# 202405272.net
KiCad netlist of a schematic drawn in EAGLE
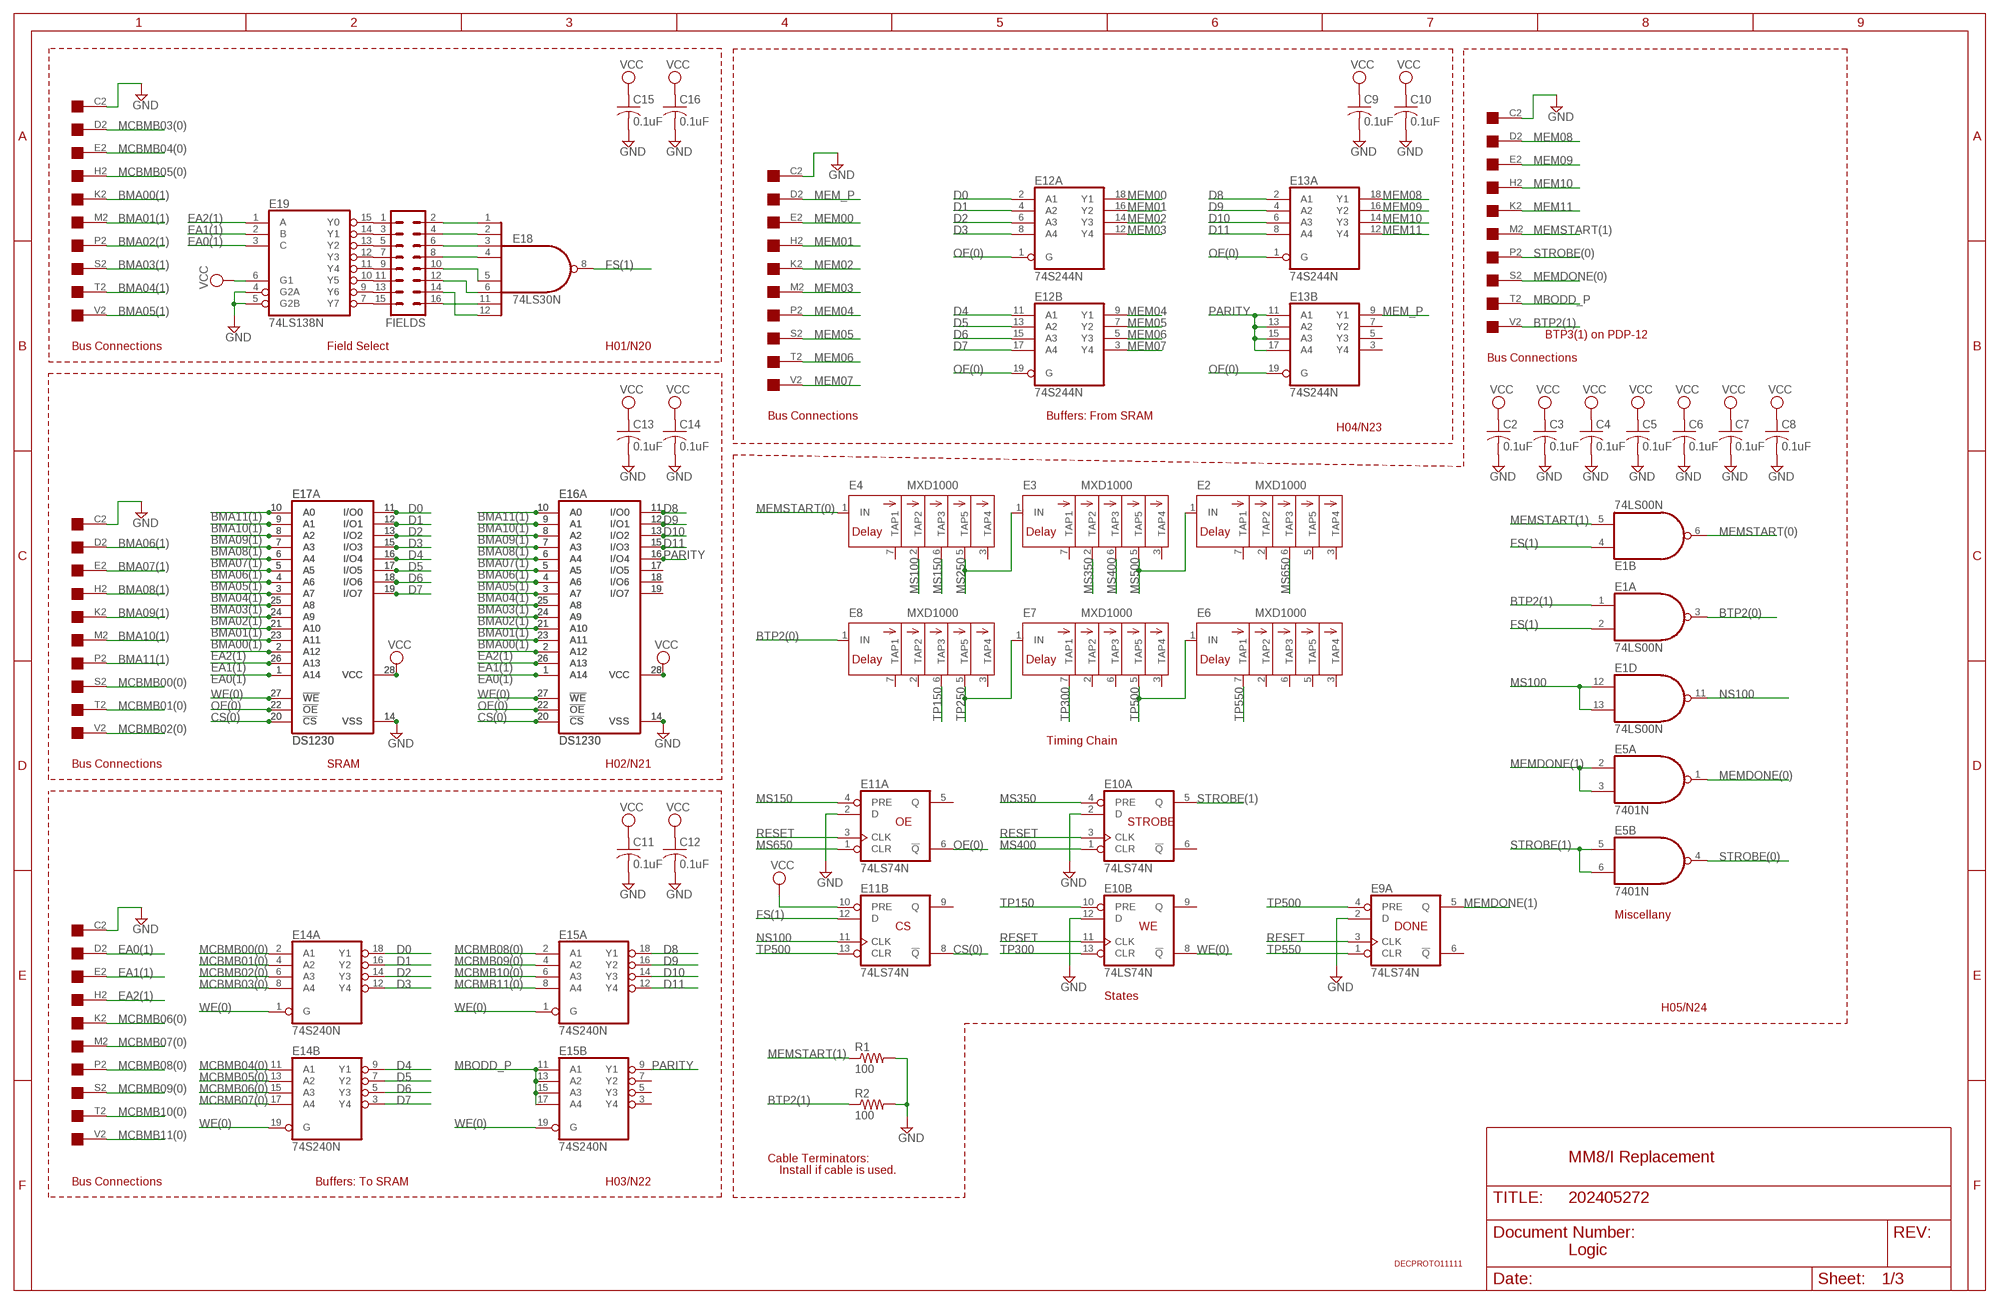
[diagram p0: schematic, sheet 1]
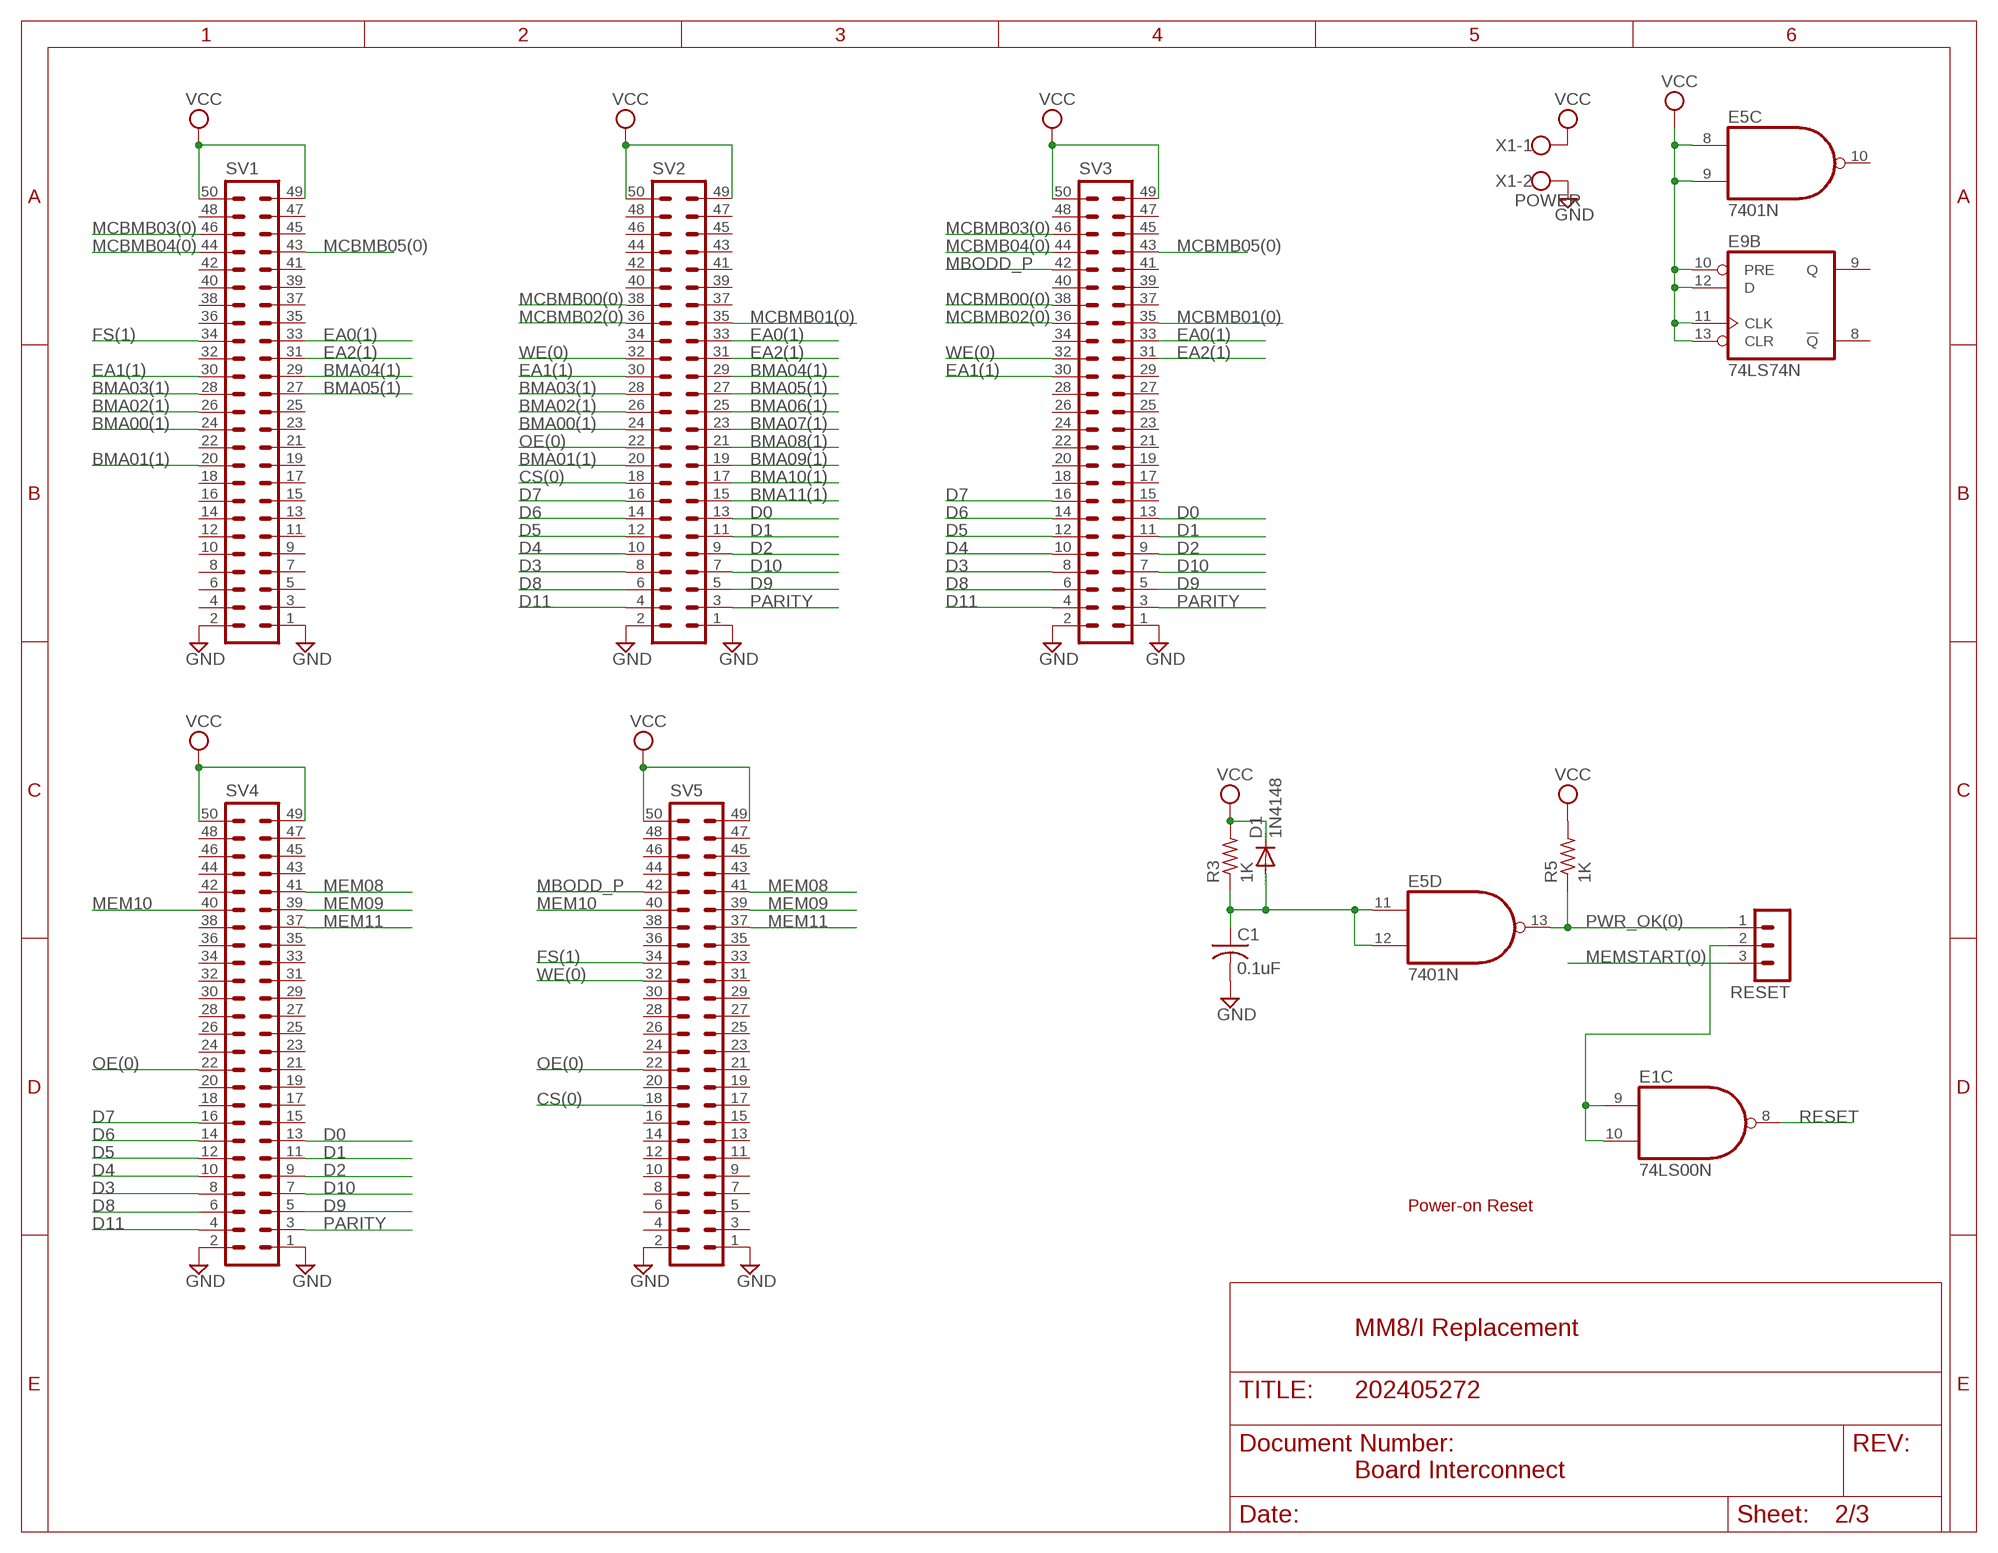
[diagram p1: schematic, sheet 2]
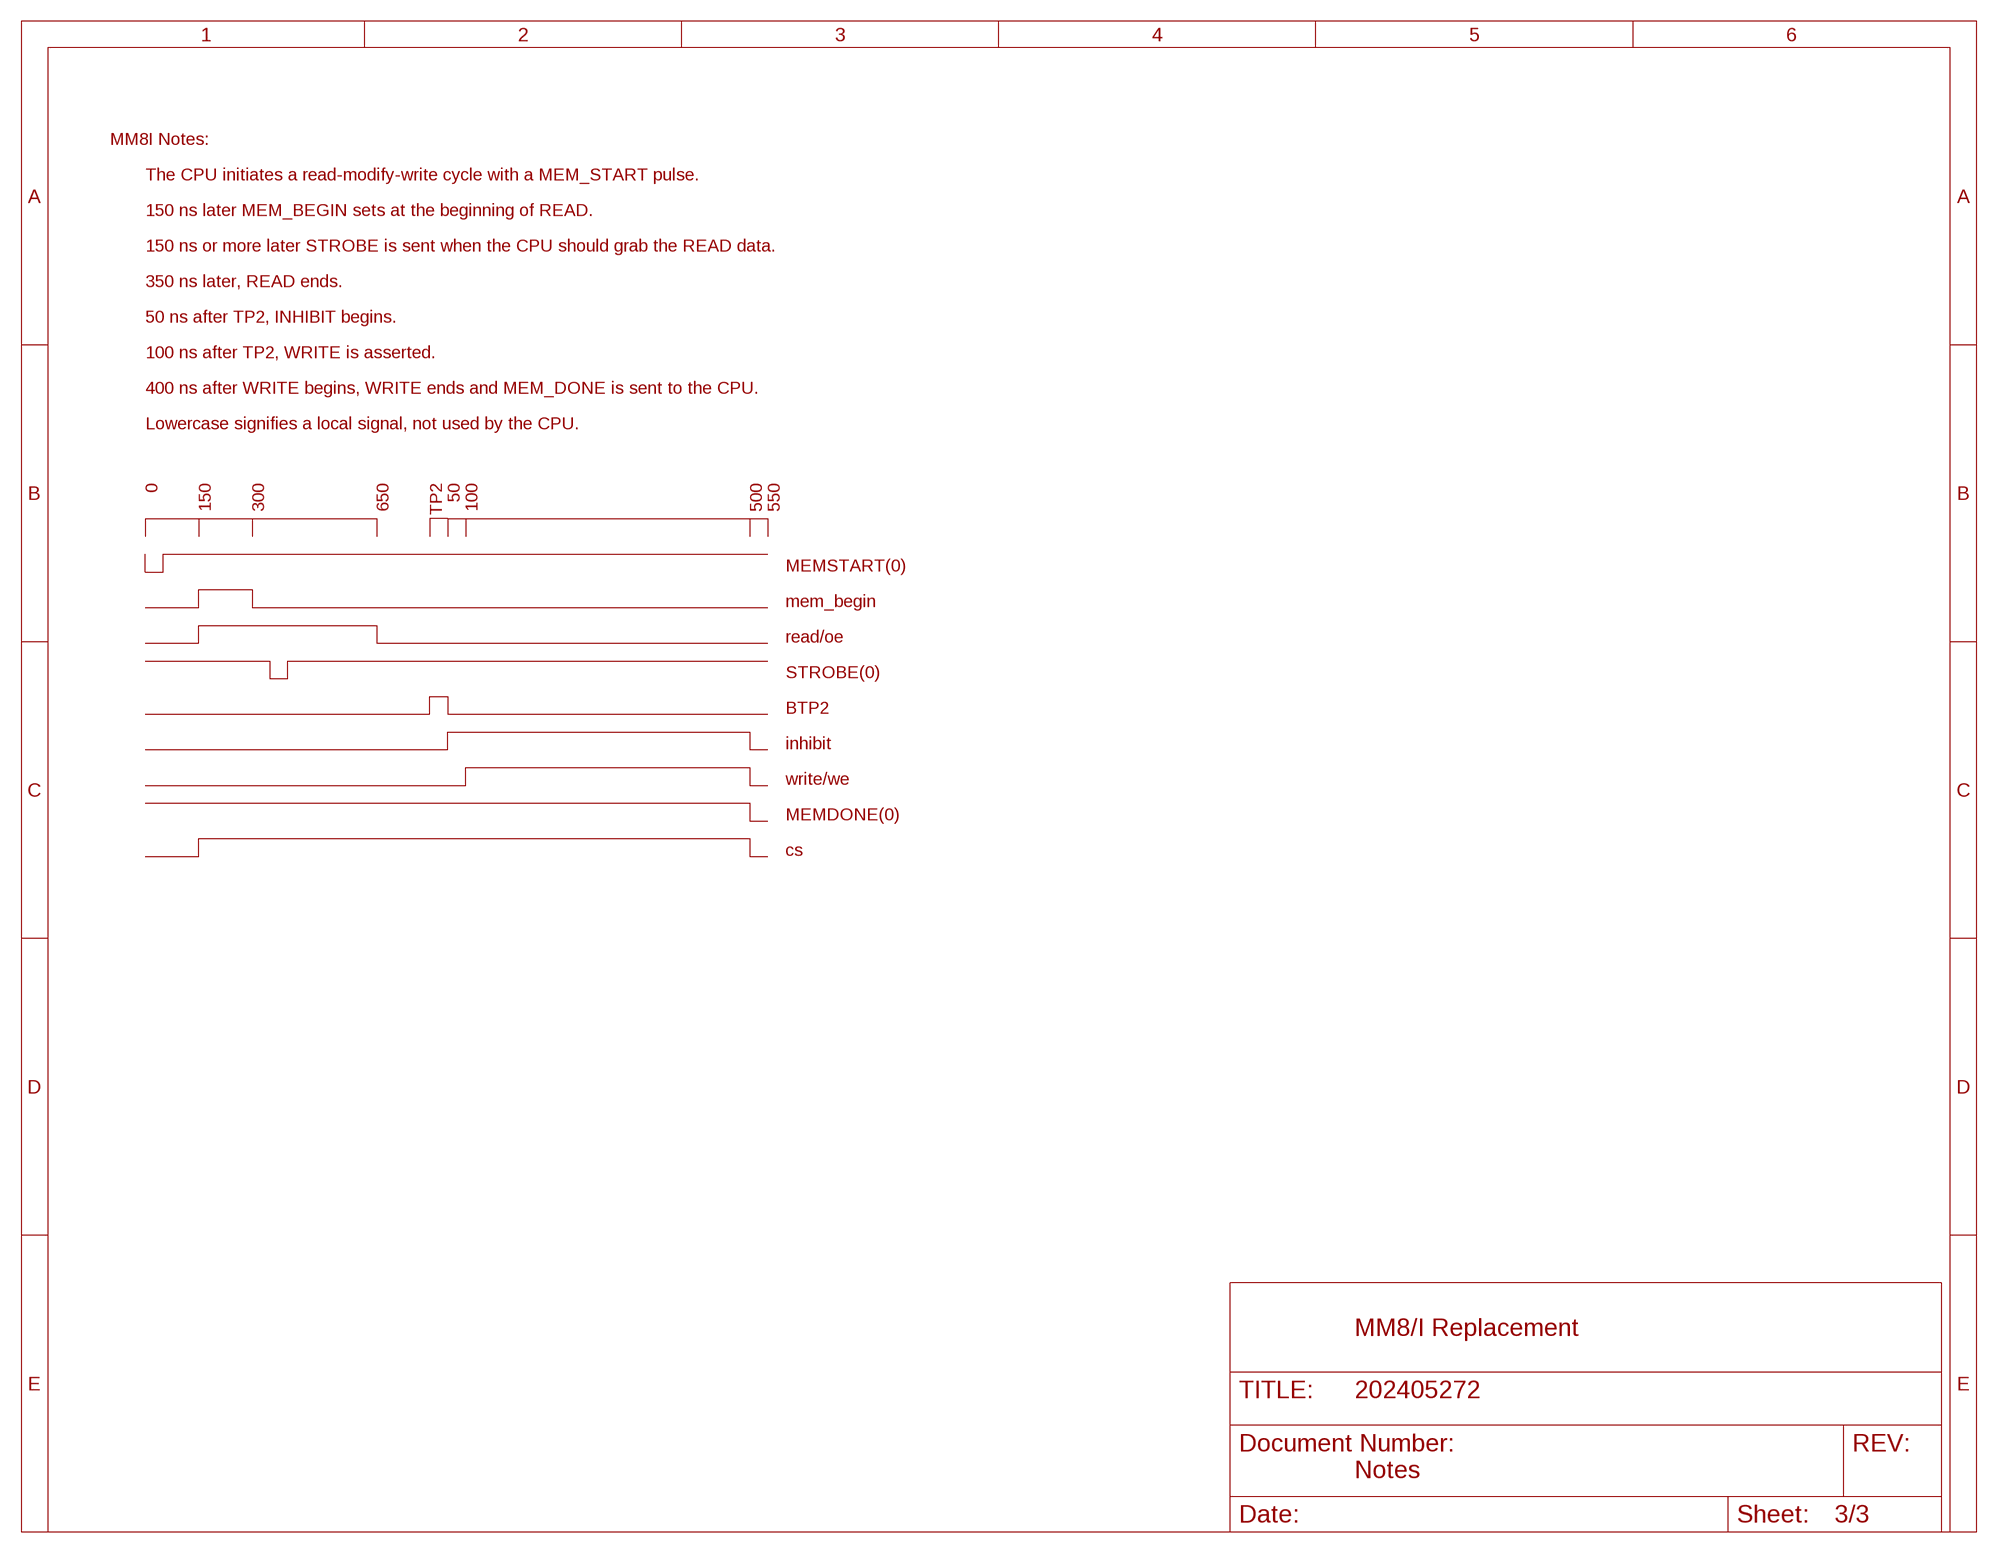
[diagram p2: schematic, sheet 3]

(export (version "E")
  (design (tool "Eeschema 10.0.6"))
  (components
    (comp (ref "C2")
      (value "0.1uF")
      (footprint "eagle-import:C050-025X075")
      (libsource (lib "eagle-import") (part "C-US050-025X075"))
    )
    (comp (ref "C3")
      (value "0.1uF")
      (footprint "eagle-import:C050-025X075")
      (libsource (lib "eagle-import") (part "C-US050-025X075"))
    )
    (comp (ref "C4")
      (value "0.1uF")
      (footprint "eagle-import:C050-025X075")
      (libsource (lib "eagle-import") (part "C-US050-025X075"))
    )
    (comp (ref "C5")
      (value "0.1uF")
      (footprint "eagle-import:C050-025X075")
      (libsource (lib "eagle-import") (part "C-US050-025X075"))
    )
    (comp (ref "C6")
      (value "0.1uF")
      (footprint "eagle-import:C050-025X075")
      (libsource (lib "eagle-import") (part "C-US050-025X075"))
    )
    (comp (ref "C7")
      (value "0.1uF")
      (footprint "eagle-import:C050-025X075")
      (libsource (lib "eagle-import") (part "C-US050-025X075"))
    )
    (comp (ref "C8")
      (value "0.1uF")
      (footprint "eagle-import:C050-025X075")
      (libsource (lib "eagle-import") (part "C-US050-025X075"))
    )
    (comp (ref "C9")
      (value "0.1uF")
      (footprint "eagle-import:C050-025X075")
      (libsource (lib "eagle-import") (part "C-US050-025X075"))
    )
    (comp (ref "C10")
      (value "0.1uF")
      (footprint "eagle-import:C050-025X075")
      (libsource (lib "eagle-import") (part "C-US050-025X075"))
    )
    (comp (ref "C11")
      (value "0.1uF")
      (footprint "eagle-import:C050-025X075")
      (libsource (lib "eagle-import") (part "C-US050-025X075"))
    )
    (comp (ref "C12")
      (value "0.1uF")
      (footprint "eagle-import:C050-025X075")
      (libsource (lib "eagle-import") (part "C-US050-025X075"))
    )
    (comp (ref "C13")
      (value "0.1uF")
      (footprint "eagle-import:C050-025X075")
      (libsource (lib "eagle-import") (part "C-US050-025X075"))
    )
    (comp (ref "C14")
      (value "0.1uF")
      (footprint "eagle-import:C050-025X075")
      (libsource (lib "eagle-import") (part "C-US050-025X075"))
    )
    (comp (ref "C15")
      (value "0.1uF")
      (footprint "eagle-import:C050-025X075")
      (libsource (lib "eagle-import") (part "C-US050-025X075"))
    )
    (comp (ref "C16")
      (value "0.1uF")
      (footprint "eagle-import:C050-025X075")
      (libsource (lib "eagle-import") (part "C-US050-025X075"))
    )
    (comp (ref "E1")
      (value "74LS00N")
      (footprint "eagle-import:DIL14")
      (libsource (lib "eagle-import") (part "7400NLS"))
    )
    (comp (ref "E2")
      (value "MXD1000")
      (footprint "eagle-import:DIL08")
      (libsource (lib "eagle-import") (part "MXD1000"))
    )
    (comp (ref "E3")
      (value "MXD1000")
      (footprint "eagle-import:DIL08")
      (libsource (lib "eagle-import") (part "MXD1000"))
    )
    (comp (ref "E4")
      (value "MXD1000")
      (footprint "eagle-import:DIL08")
      (libsource (lib "eagle-import") (part "MXD1000"))
    )
    (comp (ref "E5")
      (value "7401N")
      (footprint "eagle-import:DIL14")
      (libsource (lib "eagle-import") (part "7401NLS"))
    )
    (comp (ref "E6")
      (value "MXD1000")
      (footprint "eagle-import:DIL08")
      (libsource (lib "eagle-import") (part "MXD1000"))
    )
    (comp (ref "E7")
      (value "MXD1000")
      (footprint "eagle-import:DIL08")
      (libsource (lib "eagle-import") (part "MXD1000"))
    )
    (comp (ref "E8")
      (value "MXD1000")
      (footprint "eagle-import:DIL08")
      (libsource (lib "eagle-import") (part "MXD1000"))
    )
    (comp (ref "E9")
      (value "74LS74N")
      (footprint "eagle-import:DIL14")
      (libsource (lib "eagle-import") (part "7474NLS"))
    )
    (comp (ref "E10")
      (value "74LS74N")
      (footprint "eagle-import:DIL14")
      (libsource (lib "eagle-import") (part "7474NLS"))
    )
    (comp (ref "E11")
      (value "74LS74N")
      (footprint "eagle-import:DIL14")
      (libsource (lib "eagle-import") (part "7474NLS"))
    )
    (comp (ref "E12")
      (value "74S244N")
      (footprint "eagle-import:DIL20")
      (libsource (lib "eagle-import") (part "74244NS"))
    )
    (comp (ref "E13")
      (value "74S244N")
      (footprint "eagle-import:DIL20")
      (libsource (lib "eagle-import") (part "74244NS"))
    )
    (comp (ref "E14")
      (value "74S240N")
      (footprint "eagle-import:DIL20")
      (libsource (lib "eagle-import") (part "74240NS"))
    )
    (comp (ref "E15")
      (value "74S240N")
      (footprint "eagle-import:DIL20")
      (libsource (lib "eagle-import") (part "74240NS"))
    )
    (comp (ref "E16")
      (value "DS1230")
      (footprint "eagle-import:DIL28-6")
      (libsource (lib "eagle-import") (part "62256P"))
    )
    (comp (ref "E16A")
      (value "DS1230")
      (footprint "eagle-import:DIL28-3")
      (libsource (lib "eagle-import") (part "62832P"))
    )
    (comp (ref "E17")
      (value "DS1230")
      (footprint "eagle-import:DIL28-6")
      (libsource (lib "eagle-import") (part "62256P"))
    )
    (comp (ref "E17A")
      (value "DS1230")
      (footprint "eagle-import:DIL28-3")
      (libsource (lib "eagle-import") (part "62832P"))
    )
    (comp (ref "E18")
      (value "74LS30N")
      (footprint "eagle-import:DIL14")
      (libsource (lib "eagle-import") (part "7430NLS"))
    )
    (comp (ref "E19")
      (value "74LS138N")
      (footprint "eagle-import:DIL16")
      (libsource (lib "eagle-import") (part "74138NLS"))
    )
    (comp (ref "FIELDS")
      (value "MA08-2")
      (footprint "eagle-import:MA08-2")
      (libsource (lib "eagle-import") (part "MA08-2"))
    )
    (comp (ref "H01")
      (value "EDGE-1")
      (footprint "eagle-import:EDGE-CON1")
      (libsource (lib "eagle-import") (part "EDGE-1"))
    )
    (comp (ref "H02")
      (value "EDGE-1")
      (footprint "eagle-import:EDGE-CON1")
      (libsource (lib "eagle-import") (part "EDGE-1"))
    )
    (comp (ref "H03")
      (value "EDGE-1")
      (footprint "eagle-import:EDGE-CON1")
      (libsource (lib "eagle-import") (part "EDGE-1"))
    )
    (comp (ref "H04")
      (value "EDGE-1")
      (footprint "eagle-import:EDGE-CON1")
      (libsource (lib "eagle-import") (part "EDGE-1"))
    )
    (comp (ref "H05")
      (value "EDGE-1")
      (footprint "eagle-import:EDGE-CON1")
      (libsource (lib "eagle-import") (part "EDGE-1"))
    )
    (comp (ref "R1")
      (value "100")
      (footprint "eagle-import:0207_10")
      (libsource (lib "eagle-import") (part "R-US_0207/10"))
    )
    (comp (ref "R2")
      (value "100")
      (footprint "eagle-import:0207_10")
      (libsource (lib "eagle-import") (part "R-US_0207/10"))
    )
    (comp (ref "U$6")
      (value "DECPROTO11111")
      (footprint "eagle-import:DECPROTO11111")
      (libsource (lib "eagle-import") (part "DECPROTO11111"))
    )
    (comp (ref "C1")
      (value "0.1uF")
      (footprint "eagle-import:C050-025X075")
      (libsource (lib "eagle-import") (part "C-US050-025X075"))
    )
    (comp (ref "D1")
      (value "1N4148")
      (footprint "eagle-import:DO35-10")
      (libsource (lib "eagle-import") (part "1N4148DO35-10"))
    )
    (comp (ref "R3")
      (value "1K")
      (footprint "eagle-import:0207_10")
      (libsource (lib "eagle-import") (part "R-US_0207/10"))
    )
    (comp (ref "R5")
      (value "1K")
      (footprint "eagle-import:0207_10")
      (libsource (lib "eagle-import") (part "R-US_0207/10"))
    )
    (comp (ref "RESET")
      (value "MA03-1")
      (footprint "eagle-import:MA03-1")
      (libsource (lib "eagle-import") (part "MA03-1"))
    )
    (comp (ref "SV1")
      (value "ML50L")
      (footprint "eagle-import:ML50L")
      (libsource (lib "eagle-import") (part "ML50L"))
    )
    (comp (ref "SV2")
      (value "ML50L")
      (footprint "eagle-import:ML50L")
      (libsource (lib "eagle-import") (part "ML50L"))
    )
    (comp (ref "SV3")
      (value "ML50L")
      (footprint "eagle-import:ML50L")
      (libsource (lib "eagle-import") (part "ML50L"))
    )
    (comp (ref "SV4")
      (value "ML50L")
      (footprint "eagle-import:ML50L")
      (libsource (lib "eagle-import") (part "ML50L"))
    )
    (comp (ref "SV5")
      (value "ML50L")
      (footprint "eagle-import:ML50L")
      (libsource (lib "eagle-import") (part "ML50L"))
    )
    (comp (ref "X1")
      (value "POWER")
      (footprint "eagle-import:W237-102")
      (fields (field (name "MPN") "237-102"))
      (libsource (lib "eagle-import") (part "W237-102"))
    )
  )
  (nets
    (net (code "1") (name "BMA00(1)") (class "Default")
      (node (ref "E16") (pin "23") (pinfunction "A11_23") (pintype "input"))
      (node (ref "E16A") (pin "23") (pinfunction "A11_23") (pintype "input"))
      (node (ref "E17") (pin "23") (pinfunction "A11_23") (pintype "input"))
      (node (ref "E17A") (pin "23") (pinfunction "A11_23") (pintype "input"))
      (node (ref "H01") (pin "K2") (pinfunction "1_K2") (pintype "bidirectional"))
      (node (ref "SV1") (pin "24") (pinfunction "24_24") (pintype "passive"))
      (node (ref "SV2") (pin "24") (pinfunction "24_24") (pintype "passive"))
    )
    (net (code "2") (name "BMA01(1)") (class "Default")
      (node (ref "E16") (pin "21") (pinfunction "A10_21") (pintype "input"))
      (node (ref "E16A") (pin "21") (pinfunction "A10_21") (pintype "input"))
      (node (ref "E17") (pin "21") (pinfunction "A10_21") (pintype "input"))
      (node (ref "E17A") (pin "21") (pinfunction "A10_21") (pintype "input"))
      (node (ref "H01") (pin "M2") (pinfunction "1_M2") (pintype "bidirectional"))
      (node (ref "SV1") (pin "20") (pinfunction "20_20") (pintype "passive"))
      (node (ref "SV2") (pin "20") (pinfunction "20_20") (pintype "passive"))
    )
    (net (code "3") (name "BMA02(1)") (class "Default")
      (node (ref "E16") (pin "24") (pinfunction "A9_24") (pintype "input"))
      (node (ref "E16A") (pin "24") (pinfunction "A9_24") (pintype "input"))
      (node (ref "E17") (pin "24") (pinfunction "A9_24") (pintype "input"))
      (node (ref "E17A") (pin "24") (pinfunction "A9_24") (pintype "input"))
      (node (ref "H01") (pin "P2") (pinfunction "1_P2") (pintype "bidirectional"))
      (node (ref "SV1") (pin "26") (pinfunction "26_26") (pintype "passive"))
      (node (ref "SV2") (pin "26") (pinfunction "26_26") (pintype "passive"))
    )
    (net (code "4") (name "BMA03(1)") (class "Default")
      (node (ref "E16") (pin "25") (pinfunction "A8_25") (pintype "input"))
      (node (ref "E16A") (pin "25") (pinfunction "A8_25") (pintype "input"))
      (node (ref "E17") (pin "25") (pinfunction "A8_25") (pintype "input"))
      (node (ref "E17A") (pin "25") (pinfunction "A8_25") (pintype "input"))
      (node (ref "H01") (pin "S2") (pinfunction "1_S2") (pintype "bidirectional"))
      (node (ref "SV1") (pin "28") (pinfunction "28_28") (pintype "passive"))
      (node (ref "SV2") (pin "28") (pinfunction "28_28") (pintype "passive"))
    )
    (net (code "5") (name "BMA04(1)") (class "Default")
      (node (ref "E16") (pin "3") (pinfunction "A7_3") (pintype "input"))
      (node (ref "E16A") (pin "3") (pinfunction "A7_3") (pintype "input"))
      (node (ref "E17") (pin "3") (pinfunction "A7_3") (pintype "input"))
      (node (ref "E17A") (pin "3") (pinfunction "A7_3") (pintype "input"))
      (node (ref "H01") (pin "T2") (pinfunction "1_T2") (pintype "bidirectional"))
      (node (ref "SV1") (pin "29") (pinfunction "29_29") (pintype "passive"))
      (node (ref "SV2") (pin "29") (pinfunction "29_29") (pintype "passive"))
    )
    (net (code "6") (name "BMA05(1)") (class "Default")
      (node (ref "E16") (pin "4") (pinfunction "A6_4") (pintype "input"))
      (node (ref "E16A") (pin "4") (pinfunction "A6_4") (pintype "input"))
      (node (ref "E17") (pin "4") (pinfunction "A6_4") (pintype "input"))
      (node (ref "E17A") (pin "4") (pinfunction "A6_4") (pintype "input"))
      (node (ref "H01") (pin "V2") (pinfunction "1_V2") (pintype "bidirectional"))
      (node (ref "SV1") (pin "27") (pinfunction "27_27") (pintype "passive"))
      (node (ref "SV2") (pin "27") (pinfunction "27_27") (pintype "passive"))
    )
    (net (code "7") (name "BMA06(1)") (class "Default")
      (node (ref "E16") (pin "5") (pinfunction "A5_5") (pintype "input"))
      (node (ref "E16A") (pin "5") (pinfunction "A5_5") (pintype "input"))
      (node (ref "E17") (pin "5") (pinfunction "A5_5") (pintype "input"))
      (node (ref "E17A") (pin "5") (pinfunction "A5_5") (pintype "input"))
      (node (ref "H02") (pin "D2") (pinfunction "1_D2") (pintype "bidirectional"))
      (node (ref "SV2") (pin "25") (pinfunction "25_25") (pintype "passive"))
    )
    (net (code "8") (name "BMA07(1)") (class "Default")
      (node (ref "E16") (pin "6") (pinfunction "A4_6") (pintype "input"))
      (node (ref "E16A") (pin "6") (pinfunction "A4_6") (pintype "input"))
      (node (ref "E17") (pin "6") (pinfunction "A4_6") (pintype "input"))
      (node (ref "E17A") (pin "6") (pinfunction "A4_6") (pintype "input"))
      (node (ref "H02") (pin "E2") (pinfunction "1_E2") (pintype "bidirectional"))
      (node (ref "SV2") (pin "23") (pinfunction "23_23") (pintype "passive"))
    )
    (net (code "9") (name "BMA08(1)") (class "Default")
      (node (ref "E16") (pin "7") (pinfunction "A3_7") (pintype "input"))
      (node (ref "E16A") (pin "7") (pinfunction "A3_7") (pintype "input"))
      (node (ref "E17") (pin "7") (pinfunction "A3_7") (pintype "input"))
      (node (ref "E17A") (pin "7") (pinfunction "A3_7") (pintype "input"))
      (node (ref "H02") (pin "H2") (pinfunction "1_H2") (pintype "bidirectional"))
      (node (ref "SV2") (pin "21") (pinfunction "21_21") (pintype "passive"))
    )
    (net (code "10") (name "BMA09(1)") (class "Default")
      (node (ref "E16") (pin "8") (pinfunction "A2_8") (pintype "input"))
      (node (ref "E16A") (pin "8") (pinfunction "A2_8") (pintype "input"))
      (node (ref "E17") (pin "8") (pinfunction "A2_8") (pintype "input"))
      (node (ref "E17A") (pin "8") (pinfunction "A2_8") (pintype "input"))
      (node (ref "H02") (pin "K2") (pinfunction "1_K2") (pintype "bidirectional"))
      (node (ref "SV2") (pin "19") (pinfunction "19_19") (pintype "passive"))
    )
    (net (code "11") (name "BMA10(1)") (class "Default")
      (node (ref "E16") (pin "9") (pinfunction "A1_9") (pintype "input"))
      (node (ref "E16A") (pin "9") (pinfunction "A1_9") (pintype "input"))
      (node (ref "E17") (pin "9") (pinfunction "A1_9") (pintype "input"))
      (node (ref "E17A") (pin "9") (pinfunction "A1_9") (pintype "input"))
      (node (ref "H02") (pin "M2") (pinfunction "1_M2") (pintype "bidirectional"))
      (node (ref "SV2") (pin "17") (pinfunction "17_17") (pintype "passive"))
    )
    (net (code "12") (name "BMA11(1)") (class "Default")
      (node (ref "E16") (pin "10") (pinfunction "A0_10") (pintype "input"))
      (node (ref "E16A") (pin "10") (pinfunction "A0_10") (pintype "input"))
      (node (ref "E17") (pin "10") (pinfunction "A0_10") (pintype "input"))
      (node (ref "E17A") (pin "10") (pinfunction "A0_10") (pintype "input"))
      (node (ref "H02") (pin "P2") (pinfunction "1_P2") (pintype "bidirectional"))
      (node (ref "SV2") (pin "15") (pinfunction "15_15") (pintype "passive"))
    )
    (net (code "13") (name "BTP2(0)") (class "Default")
      (node (ref "E1") (pin "3") (pinfunction "O_3") (pintype "output"))
      (node (ref "E8") (pin "1") (pinfunction "IN_1") (pintype "input"))
    )
    (net (code "14") (name "BTP2(1)") (class "Default")
      (node (ref "E1") (pin "1") (pinfunction "I0_1") (pintype "input"))
      (node (ref "H05") (pin "V2") (pinfunction "1_V2") (pintype "bidirectional"))
      (node (ref "R2") (pin "1") (pinfunction "1_1") (pintype "passive"))
    )
    (net (code "15") (name "CS(0)") (class "Default")
      (node (ref "E11") (pin "8") (pinfunction "~{Q}_8") (pintype "output"))
      (node (ref "E16") (pin "20") (pinfunction "~{CS}_20") (pintype "input"))
      (node (ref "E16A") (pin "20") (pinfunction "~{CS}_20") (pintype "input"))
      (node (ref "E17") (pin "20") (pinfunction "~{CS}_20") (pintype "input"))
      (node (ref "E17A") (pin "20") (pinfunction "~{CS}_20") (pintype "input"))
      (node (ref "SV2") (pin "18") (pinfunction "18_18") (pintype "passive"))
      (node (ref "SV5") (pin "18") (pinfunction "18_18") (pintype "passive"))
    )
    (net (code "16") (name "D0") (class "Default")
      (node (ref "E12") (pin "2") (pinfunction "A1_2") (pintype "input"))
      (node (ref "E14") (pin "18") (pinfunction "Y1_18") (pintype "tri_state"))
      (node (ref "E17") (pin "11") (pinfunction "I/O0_11") (pintype "bidirectional"))
      (node (ref "E17A") (pin "11") (pinfunction "I/O0_11") (pintype "bidirectional"))
      (node (ref "SV2") (pin "13") (pinfunction "13_13") (pintype "passive"))
      (node (ref "SV3") (pin "13") (pinfunction "13_13") (pintype "passive"))
      (node (ref "SV4") (pin "13") (pinfunction "13_13") (pintype "passive"))
    )
    (net (code "17") (name "D1") (class "Default")
      (node (ref "E12") (pin "4") (pinfunction "A2_4") (pintype "input"))
      (node (ref "E14") (pin "16") (pinfunction "Y2_16") (pintype "tri_state"))
      (node (ref "E17") (pin "12") (pinfunction "I/O1_12") (pintype "bidirectional"))
      (node (ref "E17A") (pin "12") (pinfunction "I/O1_12") (pintype "bidirectional"))
      (node (ref "SV2") (pin "11") (pinfunction "11_11") (pintype "passive"))
      (node (ref "SV3") (pin "11") (pinfunction "11_11") (pintype "passive"))
      (node (ref "SV4") (pin "11") (pinfunction "11_11") (pintype "passive"))
    )
    (net (code "18") (name "D2") (class "Default")
      (node (ref "E12") (pin "6") (pinfunction "A3_6") (pintype "input"))
      (node (ref "E14") (pin "14") (pinfunction "Y3_14") (pintype "tri_state"))
      (node (ref "E17") (pin "13") (pinfunction "I/O2_13") (pintype "bidirectional"))
      (node (ref "E17A") (pin "13") (pinfunction "I/O2_13") (pintype "bidirectional"))
      (node (ref "SV2") (pin "9") (pinfunction "9_9") (pintype "passive"))
      (node (ref "SV3") (pin "9") (pinfunction "9_9") (pintype "passive"))
      (node (ref "SV4") (pin "9") (pinfunction "9_9") (pintype "passive"))
    )
    (net (code "19") (name "D3") (class "Default")
      (node (ref "E12") (pin "8") (pinfunction "A4_8") (pintype "input"))
      (node (ref "E14") (pin "12") (pinfunction "Y4_12") (pintype "tri_state"))
      (node (ref "E17") (pin "15") (pinfunction "I/O3_15") (pintype "bidirectional"))
      (node (ref "E17A") (pin "15") (pinfunction "I/O3_15") (pintype "bidirectional"))
      (node (ref "SV2") (pin "8") (pinfunction "8_8") (pintype "passive"))
      (node (ref "SV3") (pin "8") (pinfunction "8_8") (pintype "passive"))
      (node (ref "SV4") (pin "8") (pinfunction "8_8") (pintype "passive"))
    )
    (net (code "20") (name "D4") (class "Default")
      (node (ref "E12") (pin "11") (pinfunction "A1_11") (pintype "input"))
      (node (ref "E14") (pin "9") (pinfunction "Y1_9") (pintype "tri_state"))
      (node (ref "E17") (pin "16") (pinfunction "I/O4_16") (pintype "bidirectional"))
      (node (ref "E17A") (pin "16") (pinfunction "I/O4_16") (pintype "bidirectional"))
      (node (ref "SV2") (pin "10") (pinfunction "10_10") (pintype "passive"))
      (node (ref "SV3") (pin "10") (pinfunction "10_10") (pintype "passive"))
      (node (ref "SV4") (pin "10") (pinfunction "10_10") (pintype "passive"))
    )
    (net (code "21") (name "D5") (class "Default")
      (node (ref "E12") (pin "13") (pinfunction "A2_13") (pintype "input"))
      (node (ref "E14") (pin "7") (pinfunction "Y2_7") (pintype "tri_state"))
      (node (ref "E17") (pin "17") (pinfunction "I/O5_17") (pintype "bidirectional"))
      (node (ref "E17A") (pin "17") (pinfunction "I/O5_17") (pintype "bidirectional"))
      (node (ref "SV2") (pin "12") (pinfunction "12_12") (pintype "passive"))
      (node (ref "SV3") (pin "12") (pinfunction "12_12") (pintype "passive"))
      (node (ref "SV4") (pin "12") (pinfunction "12_12") (pintype "passive"))
    )
    (net (code "22") (name "D6") (class "Default")
      (node (ref "E12") (pin "15") (pinfunction "A3_15") (pintype "input"))
      (node (ref "E14") (pin "5") (pinfunction "Y3_5") (pintype "tri_state"))
      (node (ref "E17") (pin "18") (pinfunction "I/O6_18") (pintype "bidirectional"))
      (node (ref "E17A") (pin "18") (pinfunction "I/O6_18") (pintype "bidirectional"))
      (node (ref "SV2") (pin "14") (pinfunction "14_14") (pintype "passive"))
      (node (ref "SV3") (pin "14") (pinfunction "14_14") (pintype "passive"))
      (node (ref "SV4") (pin "14") (pinfunction "14_14") (pintype "passive"))
    )
    (net (code "23") (name "D7") (class "Default")
      (node (ref "E12") (pin "17") (pinfunction "A4_17") (pintype "input"))
      (node (ref "E14") (pin "3") (pinfunction "Y4_3") (pintype "tri_state"))
      (node (ref "E17") (pin "19") (pinfunction "I/O7_19") (pintype "bidirectional"))
      (node (ref "E17A") (pin "19") (pinfunction "I/O7_19") (pintype "bidirectional"))
      (node (ref "SV2") (pin "16") (pinfunction "16_16") (pintype "passive"))
      (node (ref "SV3") (pin "16") (pinfunction "16_16") (pintype "passive"))
      (node (ref "SV4") (pin "16") (pinfunction "16_16") (pintype "passive"))
    )
    (net (code "24") (name "D8") (class "Default")
      (node (ref "E13") (pin "2") (pinfunction "A1_2") (pintype "input"))
      (node (ref "E15") (pin "18") (pinfunction "Y1_18") (pintype "tri_state"))
      (node (ref "E16") (pin "11") (pinfunction "I/O0_11") (pintype "bidirectional"))
      (node (ref "E16A") (pin "11") (pinfunction "I/O0_11") (pintype "bidirectional"))
      (node (ref "SV2") (pin "6") (pinfunction "6_6") (pintype "passive"))
      (node (ref "SV3") (pin "6") (pinfunction "6_6") (pintype "passive"))
      (node (ref "SV4") (pin "6") (pinfunction "6_6") (pintype "passive"))
    )
    (net (code "25") (name "D9") (class "Default")
      (node (ref "E13") (pin "4") (pinfunction "A2_4") (pintype "input"))
      (node (ref "E15") (pin "16") (pinfunction "Y2_16") (pintype "tri_state"))
      (node (ref "E16") (pin "12") (pinfunction "I/O1_12") (pintype "bidirectional"))
      (node (ref "E16A") (pin "12") (pinfunction "I/O1_12") (pintype "bidirectional"))
      (node (ref "SV2") (pin "5") (pinfunction "5_5") (pintype "passive"))
      (node (ref "SV3") (pin "5") (pinfunction "5_5") (pintype "passive"))
      (node (ref "SV4") (pin "5") (pinfunction "5_5") (pintype "passive"))
    )
    (net (code "26") (name "D10") (class "Default")
      (node (ref "E13") (pin "6") (pinfunction "A3_6") (pintype "input"))
      (node (ref "E15") (pin "14") (pinfunction "Y3_14") (pintype "tri_state"))
      (node (ref "E16") (pin "13") (pinfunction "I/O2_13") (pintype "bidirectional"))
      (node (ref "E16A") (pin "13") (pinfunction "I/O2_13") (pintype "bidirectional"))
      (node (ref "SV2") (pin "7") (pinfunction "7_7") (pintype "passive"))
      (node (ref "SV3") (pin "7") (pinfunction "7_7") (pintype "passive"))
      (node (ref "SV4") (pin "7") (pinfunction "7_7") (pintype "passive"))
    )
    (net (code "27") (name "D11") (class "Default")
      (node (ref "E13") (pin "8") (pinfunction "A4_8") (pintype "input"))
      (node (ref "E15") (pin "12") (pinfunction "Y4_12") (pintype "tri_state"))
      (node (ref "E16") (pin "15") (pinfunction "I/O3_15") (pintype "bidirectional"))
      (node (ref "E16A") (pin "15") (pinfunction "I/O3_15") (pintype "bidirectional"))
      (node (ref "SV2") (pin "4") (pinfunction "4_4") (pintype "passive"))
      (node (ref "SV3") (pin "4") (pinfunction "4_4") (pintype "passive"))
      (node (ref "SV4") (pin "4") (pinfunction "4_4") (pintype "passive"))
    )
    (net (code "28") (name "EA0(1)") (class "Default")
      (node (ref "E16") (pin "1") (pinfunction "A14_1") (pintype "input"))
      (node (ref "E16A") (pin "1") (pinfunction "A14_1") (pintype "input"))
      (node (ref "E17") (pin "1") (pinfunction "A14_1") (pintype "input"))
      (node (ref "E17A") (pin "1") (pinfunction "A14_1") (pintype "input"))
      (node (ref "E19") (pin "3") (pinfunction "C_3") (pintype "input"))
      (node (ref "H03") (pin "D2") (pinfunction "1_D2") (pintype "bidirectional"))
      (node (ref "SV1") (pin "33") (pinfunction "33_33") (pintype "passive"))
      (node (ref "SV2") (pin "33") (pinfunction "33_33") (pintype "passive"))
      (node (ref "SV3") (pin "33") (pinfunction "33_33") (pintype "passive"))
    )
    (net (code "29") (name "EA1(1)") (class "Default")
      (node (ref "E16") (pin "26") (pinfunction "A13_26") (pintype "input"))
      (node (ref "E16A") (pin "26") (pinfunction "A13_26") (pintype "input"))
      (node (ref "E17") (pin "26") (pinfunction "A13_26") (pintype "input"))
      (node (ref "E17A") (pin "26") (pinfunction "A13_26") (pintype "input"))
      (node (ref "E19") (pin "2") (pinfunction "B_2") (pintype "input"))
      (node (ref "H03") (pin "E2") (pinfunction "1_E2") (pintype "bidirectional"))
      (node (ref "SV1") (pin "30") (pinfunction "30_30") (pintype "passive"))
      (node (ref "SV2") (pin "30") (pinfunction "30_30") (pintype "passive"))
      (node (ref "SV3") (pin "30") (pinfunction "30_30") (pintype "passive"))
    )
    (net (code "30") (name "EA2(1)") (class "Default")
      (node (ref "E16") (pin "2") (pinfunction "A12_2") (pintype "input"))
      (node (ref "E16A") (pin "2") (pinfunction "A12_2") (pintype "input"))
      (node (ref "E17") (pin "2") (pinfunction "A12_2") (pintype "input"))
      (node (ref "E17A") (pin "2") (pinfunction "A12_2") (pintype "input"))
      (node (ref "E19") (pin "1") (pinfunction "A_1") (pintype "input"))
      (node (ref "H03") (pin "H2") (pinfunction "1_H2") (pintype "bidirectional"))
      (node (ref "SV1") (pin "31") (pinfunction "31_31") (pintype "passive"))
      (node (ref "SV2") (pin "31") (pinfunction "31_31") (pintype "passive"))
      (node (ref "SV3") (pin "31") (pinfunction "31_31") (pintype "passive"))
    )
    (net (code "31") (name "FS(1)") (class "Default")
      (node (ref "E1") (pin "2") (pinfunction "I1_2") (pintype "input"))
      (node (ref "E1") (pin "4") (pinfunction "I0_4") (pintype "input"))
      (node (ref "E11") (pin "12") (pinfunction "D_12") (pintype "input"))
      (node (ref "E18") (pin "8") (pinfunction "O_8") (pintype "output"))
      (node (ref "SV1") (pin "34") (pinfunction "34_34") (pintype "passive"))
      (node (ref "SV5") (pin "34") (pinfunction "34_34") (pintype "passive"))
    )
    (net (code "32") (name "GND") (class "Default")
      (node (ref "C1") (pin "2") (pinfunction "2_2") (pintype "passive"))
      (node (ref "C10") (pin "2") (pinfunction "2_2") (pintype "passive"))
      (node (ref "C11") (pin "2") (pinfunction "2_2") (pintype "passive"))
      (node (ref "C12") (pin "2") (pinfunction "2_2") (pintype "passive"))
      (node (ref "C13") (pin "2") (pinfunction "2_2") (pintype "passive"))
      (node (ref "C14") (pin "2") (pinfunction "2_2") (pintype "passive"))
      (node (ref "C15") (pin "2") (pinfunction "2_2") (pintype "passive"))
      (node (ref "C16") (pin "2") (pinfunction "2_2") (pintype "passive"))
      (node (ref "C2") (pin "2") (pinfunction "2_2") (pintype "passive"))
      (node (ref "C3") (pin "2") (pinfunction "2_2") (pintype "passive"))
      (node (ref "C4") (pin "2") (pinfunction "2_2") (pintype "passive"))
      (node (ref "C5") (pin "2") (pinfunction "2_2") (pintype "passive"))
      (node (ref "C6") (pin "2") (pinfunction "2_2") (pintype "passive"))
      (node (ref "C7") (pin "2") (pinfunction "2_2") (pintype "passive"))
      (node (ref "C8") (pin "2") (pinfunction "2_2") (pintype "passive"))
      (node (ref "C9") (pin "2") (pinfunction "2_2") (pintype "passive"))
      (node (ref "E10") (pin "12") (pinfunction "D_12") (pintype "input"))
      (node (ref "E10") (pin "2") (pinfunction "D_2") (pintype "input"))
      (node (ref "E11") (pin "2") (pinfunction "D_2") (pintype "input"))
      (node (ref "E16") (pin "14") (pinfunction "VSS_14") (pintype "power_in"))
      (node (ref "E16A") (pin "14") (pinfunction "VSS_14") (pintype "power_in"))
      (node (ref "E17") (pin "14") (pinfunction "VSS_14") (pintype "power_in"))
      (node (ref "E17A") (pin "14") (pinfunction "VSS_14") (pintype "power_in"))
      (node (ref "E19") (pin "4") (pinfunction "G2A_4") (pintype "input"))
      (node (ref "E19") (pin "5") (pinfunction "G2B_5") (pintype "input"))
      (node (ref "E9") (pin "2") (pinfunction "D_2") (pintype "input"))
      (node (ref "H01") (pin "C2") (pinfunction "1_C2") (pintype "bidirectional"))
      (node (ref "H02") (pin "C2") (pinfunction "1_C2") (pintype "bidirectional"))
      (node (ref "H03") (pin "C2") (pinfunction "1_C2") (pintype "bidirectional"))
      (node (ref "H04") (pin "C2") (pinfunction "1_C2") (pintype "bidirectional"))
      (node (ref "H05") (pin "C2") (pinfunction "1_C2") (pintype "bidirectional"))
      (node (ref "R1") (pin "2") (pinfunction "2_2") (pintype "passive"))
      (node (ref "R2") (pin "2") (pinfunction "2_2") (pintype "passive"))
      (node (ref "SV1") (pin "1") (pinfunction "1_1") (pintype "passive"))
      (node (ref "SV1") (pin "2") (pinfunction "2_2") (pintype "passive"))
      (node (ref "SV2") (pin "1") (pinfunction "1_1") (pintype "passive"))
      (node (ref "SV2") (pin "2") (pinfunction "2_2") (pintype "passive"))
      (node (ref "SV3") (pin "1") (pinfunction "1_1") (pintype "passive"))
      (node (ref "SV3") (pin "2") (pinfunction "2_2") (pintype "passive"))
      (node (ref "SV4") (pin "1") (pinfunction "1_1") (pintype "passive"))
      (node (ref "SV4") (pin "2") (pinfunction "2_2") (pintype "passive"))
      (node (ref "SV5") (pin "1") (pinfunction "1_1") (pintype "passive"))
      (node (ref "SV5") (pin "2") (pinfunction "2_2") (pintype "passive"))
      (node (ref "X1") (pin "2") (pinfunction "KL_2") (pintype "passive"))
    )
    (net (code "33") (name "MBODD_P") (class "Default")
      (node (ref "E15") (pin "11") (pinfunction "A1_11") (pintype "input"))
      (node (ref "E15") (pin "13") (pinfunction "A2_13") (pintype "input"))
      (node (ref "E15") (pin "15") (pinfunction "A3_15") (pintype "input"))
      (node (ref "E15") (pin "17") (pinfunction "A4_17") (pintype "input"))
      (node (ref "H05") (pin "T2") (pinfunction "1_T2") (pintype "bidirectional"))
      (node (ref "SV3") (pin "42") (pinfunction "42_42") (pintype "passive"))
      (node (ref "SV5") (pin "42") (pinfunction "42_42") (pintype "passive"))
    )
    (net (code "34") (name "MCBMB00(0)") (class "Default")
      (node (ref "E14") (pin "2") (pinfunction "A1_2") (pintype "input"))
      (node (ref "H02") (pin "S2") (pinfunction "1_S2") (pintype "bidirectional"))
      (node (ref "SV2") (pin "38") (pinfunction "38_38") (pintype "passive"))
      (node (ref "SV3") (pin "38") (pinfunction "38_38") (pintype "passive"))
    )
    (net (code "35") (name "MCBMB01(0)") (class "Default")
      (node (ref "E14") (pin "4") (pinfunction "A2_4") (pintype "input"))
      (node (ref "H02") (pin "T2") (pinfunction "1_T2") (pintype "bidirectional"))
      (node (ref "SV2") (pin "35") (pinfunction "35_35") (pintype "passive"))
      (node (ref "SV3") (pin "35") (pinfunction "35_35") (pintype "passive"))
    )
    (net (code "36") (name "MCBMB02(0)") (class "Default")
      (node (ref "E14") (pin "6") (pinfunction "A3_6") (pintype "input"))
      (node (ref "H02") (pin "V2") (pinfunction "1_V2") (pintype "bidirectional"))
      (node (ref "SV2") (pin "36") (pinfunction "36_36") (pintype "passive"))
      (node (ref "SV3") (pin "36") (pinfunction "36_36") (pintype "passive"))
    )
    (net (code "37") (name "MCBMB03(0)") (class "Default")
      (node (ref "E14") (pin "8") (pinfunction "A4_8") (pintype "input"))
      (node (ref "H01") (pin "D2") (pinfunction "1_D2") (pintype "bidirectional"))
      (node (ref "SV1") (pin "46") (pinfunction "46_46") (pintype "passive"))
      (node (ref "SV3") (pin "46") (pinfunction "46_46") (pintype "passive"))
    )
    (net (code "38") (name "MCBMB04(0)") (class "Default")
      (node (ref "E14") (pin "11") (pinfunction "A1_11") (pintype "input"))
      (node (ref "H01") (pin "E2") (pinfunction "1_E2") (pintype "bidirectional"))
      (node (ref "SV1") (pin "44") (pinfunction "44_44") (pintype "passive"))
      (node (ref "SV3") (pin "44") (pinfunction "44_44") (pintype "passive"))
    )
    (net (code "39") (name "MCBMB05(0)") (class "Default")
      (node (ref "E14") (pin "13") (pinfunction "A2_13") (pintype "input"))
      (node (ref "H01") (pin "H2") (pinfunction "1_H2") (pintype "bidirectional"))
      (node (ref "SV1") (pin "43") (pinfunction "43_43") (pintype "passive"))
      (node (ref "SV3") (pin "43") (pinfunction "43_43") (pintype "passive"))
    )
    (net (code "40") (name "MCBMB06(0)") (class "Default")
      (node (ref "E14") (pin "15") (pinfunction "A3_15") (pintype "input"))
      (node (ref "H03") (pin "K2") (pinfunction "1_K2") (pintype "bidirectional"))
    )
    (net (code "41") (name "MCBMB07(0)") (class "Default")
      (node (ref "E14") (pin "17") (pinfunction "A4_17") (pintype "input"))
      (node (ref "H03") (pin "M2") (pinfunction "1_M2") (pintype "bidirectional"))
    )
    (net (code "42") (name "MCBMB08(0)") (class "Default")
      (node (ref "E15") (pin "2") (pinfunction "A1_2") (pintype "input"))
      (node (ref "H03") (pin "P2") (pinfunction "1_P2") (pintype "bidirectional"))
    )
    (net (code "43") (name "MCBMB09(0)") (class "Default")
      (node (ref "E15") (pin "4") (pinfunction "A2_4") (pintype "input"))
      (node (ref "H03") (pin "S2") (pinfunction "1_S2") (pintype "bidirectional"))
    )
    (net (code "44") (name "MCBMB10(0)") (class "Default")
      (node (ref "E15") (pin "6") (pinfunction "A3_6") (pintype "input"))
      (node (ref "H03") (pin "T2") (pinfunction "1_T2") (pintype "bidirectional"))
    )
    (net (code "45") (name "MCBMB11(0)") (class "Default")
      (node (ref "E15") (pin "8") (pinfunction "A4_8") (pintype "input"))
      (node (ref "H03") (pin "V2") (pinfunction "1_V2") (pintype "bidirectional"))
    )
    (net (code "46") (name "MEM00") (class "Default")
      (node (ref "E12") (pin "18") (pinfunction "Y1_18") (pintype "tri_state"))
      (node (ref "H04") (pin "E2") (pinfunction "1_E2") (pintype "bidirectional"))
    )
    (net (code "47") (name "MEM01") (class "Default")
      (node (ref "E12") (pin "16") (pinfunction "Y2_16") (pintype "tri_state"))
      (node (ref "H04") (pin "H2") (pinfunction "1_H2") (pintype "bidirectional"))
    )
    (net (code "48") (name "MEM02") (class "Default")
      (node (ref "E12") (pin "14") (pinfunction "Y3_14") (pintype "tri_state"))
      (node (ref "H04") (pin "K2") (pinfunction "1_K2") (pintype "bidirectional"))
    )
    (net (code "49") (name "MEM03") (class "Default")
      (node (ref "E12") (pin "12") (pinfunction "Y4_12") (pintype "tri_state"))
      (node (ref "H04") (pin "M2") (pinfunction "1_M2") (pintype "bidirectional"))
    )
    (net (code "50") (name "MEM04") (class "Default")
      (node (ref "E12") (pin "9") (pinfunction "Y1_9") (pintype "tri_state"))
      (node (ref "H04") (pin "P2") (pinfunction "1_P2") (pintype "bidirectional"))
    )
    (net (code "51") (name "MEM05") (class "Default")
      (node (ref "E12") (pin "7") (pinfunction "Y2_7") (pintype "tri_state"))
      (node (ref "H04") (pin "S2") (pinfunction "1_S2") (pintype "bidirectional"))
    )
    (net (code "52") (name "MEM06") (class "Default")
      (node (ref "E12") (pin "5") (pinfunction "Y3_5") (pintype "tri_state"))
      (node (ref "H04") (pin "T2") (pinfunction "1_T2") (pintype "bidirectional"))
    )
    (net (code "53") (name "MEM07") (class "Default")
      (node (ref "E12") (pin "3") (pinfunction "Y4_3") (pintype "tri_state"))
      (node (ref "H04") (pin "V2") (pinfunction "1_V2") (pintype "bidirectional"))
    )
    (net (code "54") (name "MEM08") (class "Default")
      (node (ref "E13") (pin "18") (pinfunction "Y1_18") (pintype "tri_state"))
      (node (ref "H05") (pin "D2") (pinfunction "1_D2") (pintype "bidirectional"))
      (node (ref "SV4") (pin "41") (pinfunction "41_41") (pintype "passive"))
      (node (ref "SV5") (pin "41") (pinfunction "41_41") (pintype "passive"))
    )
    (net (code "55") (name "MEM09") (class "Default")
      (node (ref "E13") (pin "16") (pinfunction "Y2_16") (pintype "tri_state"))
      (node (ref "H05") (pin "E2") (pinfunction "1_E2") (pintype "bidirectional"))
      (node (ref "SV4") (pin "39") (pinfunction "39_39") (pintype "passive"))
      (node (ref "SV5") (pin "39") (pinfunction "39_39") (pintype "passive"))
    )
    (net (code "56") (name "MEM10") (class "Default")
      (node (ref "E13") (pin "14") (pinfunction "Y3_14") (pintype "tri_state"))
      (node (ref "H05") (pin "H2") (pinfunction "1_H2") (pintype "bidirectional"))
      (node (ref "SV4") (pin "40") (pinfunction "40_40") (pintype "passive"))
      (node (ref "SV5") (pin "40") (pinfunction "40_40") (pintype "passive"))
    )
    (net (code "57") (name "MEM11") (class "Default")
      (node (ref "E13") (pin "12") (pinfunction "Y4_12") (pintype "tri_state"))
      (node (ref "H05") (pin "K2") (pinfunction "1_K2") (pintype "bidirectional"))
      (node (ref "SV4") (pin "37") (pinfunction "37_37") (pintype "passive"))
      (node (ref "SV5") (pin "37") (pinfunction "37_37") (pintype "passive"))
    )
    (net (code "58") (name "MEMDONE(0)") (class "Default")
      (node (ref "E5") (pin "1") (pinfunction "O_1") (pintype "open_collector"))
      (node (ref "H05") (pin "S2") (pinfunction "1_S2") (pintype "bidirectional"))
    )
    (net (code "59") (name "MEMDONE(1)") (class "Default")
      (node (ref "E5") (pin "2") (pinfunction "I0_2") (pintype "input"))
      (node (ref "E5") (pin "3") (pinfunction "I1_3") (pintype "input"))
      (node (ref "E9") (pin "5") (pinfunction "Q_5") (pintype "output"))
    )
    (net (code "60") (name "MEMSTART(0)") (class "Default")
      (node (ref "E1") (pin "6") (pinfunction "O_6") (pintype "output"))
      (node (ref "E4") (pin "1") (pinfunction "IN_1") (pintype "input"))
      (node (ref "RESET") (pin "3") (pinfunction "3_3") (pintype "passive"))
    )
    (net (code "61") (name "MEMSTART(1)") (class "Default")
      (node (ref "E1") (pin "5") (pinfunction "I1_5") (pintype "input"))
      (node (ref "H05") (pin "M2") (pinfunction "1_M2") (pintype "bidirectional"))
      (node (ref "R1") (pin "1") (pinfunction "1_1") (pintype "passive"))
    )
    (net (code "62") (name "MEM_P") (class "Default")
      (node (ref "E13") (pin "9") (pinfunction "Y1_9") (pintype "tri_state"))
      (node (ref "H04") (pin "D2") (pinfunction "1_D2") (pintype "bidirectional"))
    )
    (net (code "63") (name "MS100") (class "Default")
      (node (ref "E1") (pin "12") (pinfunction "I0_12") (pintype "input"))
      (node (ref "E1") (pin "13") (pinfunction "I1_13") (pintype "input"))
      (node (ref "E4") (pin "2") (pinfunction "TAP2_2") (pintype "output"))
    )
    (net (code "64") (name "MS150") (class "Default")
      (node (ref "E11") (pin "4") (pinfunction "PRE_4") (pintype "input"))
      (node (ref "E4") (pin "6") (pinfunction "TAP3_6") (pintype "output"))
    )
    (net (code "65") (name "MS250") (class "Default")
      (node (ref "E3") (pin "1") (pinfunction "IN_1") (pintype "input"))
      (node (ref "E4") (pin "5") (pinfunction "TAP5_5") (pintype "output"))
    )
    (net (code "66") (name "MS350") (class "Default")
      (node (ref "E10") (pin "4") (pinfunction "PRE_4") (pintype "input"))
      (node (ref "E3") (pin "2") (pinfunction "TAP2_2") (pintype "output"))
    )
    (net (code "67") (name "MS400") (class "Default")
      (node (ref "E10") (pin "1") (pinfunction "CLR_1") (pintype "input"))
      (node (ref "E3") (pin "6") (pinfunction "TAP3_6") (pintype "output"))
    )
    (net (code "68") (name "MS500") (class "Default")
      (node (ref "E2") (pin "1") (pinfunction "IN_1") (pintype "input"))
      (node (ref "E3") (pin "5") (pinfunction "TAP5_5") (pintype "output"))
    )
    (net (code "69") (name "MS650") (class "Default")
      (node (ref "E11") (pin "1") (pinfunction "CLR_1") (pintype "input"))
      (node (ref "E2") (pin "6") (pinfunction "TAP3_6") (pintype "output"))
    )
    (net (code "70") (name "NS100") (class "Default")
      (node (ref "E1") (pin "11") (pinfunction "O_11") (pintype "output"))
      (node (ref "E11") (pin "11") (pinfunction "CLK_11") (pintype "input"))
    )
    (net (code "71") (name "Net-(E1C-I0)") (class "Default")
      (node (ref "E1") (pin "10") (pinfunction "I1_10") (pintype "input"))
      (node (ref "E1") (pin "9") (pinfunction "I0_9") (pintype "input"))
      (node (ref "RESET") (pin "2") (pinfunction "2_2") (pintype "passive"))
    )
    (net (code "72") (name "Net-(E5D-I0)") (class "Default")
      (node (ref "C1") (pin "1") (pinfunction "1_1") (pintype "passive"))
      (node (ref "D1") (pin "A") (pinfunction "A_A") (pintype "passive"))
      (node (ref "E5") (pin "11") (pinfunction "I0_11") (pintype "input"))
      (node (ref "E5") (pin "12") (pinfunction "I1_12") (pintype "input"))
      (node (ref "R3") (pin "1") (pinfunction "1_1") (pintype "passive"))
    )
    (net (code "73") (name "Net-(E16-I{slash}O5)") (class "Default")
      (node (ref "E16") (pin "17") (pinfunction "I/O5_17") (pintype "bidirectional"))
      (node (ref "E16A") (pin "17") (pinfunction "I/O5_17") (pintype "bidirectional"))
    )
    (net (code "74") (name "Net-(E16-I{slash}O6)") (class "Default")
      (node (ref "E16") (pin "18") (pinfunction "I/O6_18") (pintype "bidirectional"))
      (node (ref "E16A") (pin "18") (pinfunction "I/O6_18") (pintype "bidirectional"))
    )
    (net (code "75") (name "Net-(E16-I{slash}O7)") (class "Default")
      (node (ref "E16") (pin "19") (pinfunction "I/O7_19") (pintype "bidirectional"))
      (node (ref "E16A") (pin "19") (pinfunction "I/O7_19") (pintype "bidirectional"))
    )
    (net (code "76") (name "Net-(E18A-I0)") (class "Default")
      (node (ref "E18") (pin "1") (pinfunction "I0_1") (pintype "input"))
      (node (ref "FIELDS") (pin "2") (pinfunction "2_2") (pintype "passive"))
    )
    (net (code "77") (name "Net-(E18A-I1)") (class "Default")
      (node (ref "E18") (pin "2") (pinfunction "I1_2") (pintype "input"))
      (node (ref "FIELDS") (pin "4") (pinfunction "4_4") (pintype "passive"))
    )
    (net (code "78") (name "Net-(E18A-I2)") (class "Default")
      (node (ref "E18") (pin "3") (pinfunction "I2_3") (pintype "input"))
      (node (ref "FIELDS") (pin "6") (pinfunction "6_6") (pintype "passive"))
    )
    (net (code "79") (name "Net-(E18A-I3)") (class "Default")
      (node (ref "E18") (pin "4") (pinfunction "I3_4") (pintype "input"))
      (node (ref "FIELDS") (pin "8") (pinfunction "8_8") (pintype "passive"))
    )
    (net (code "80") (name "Net-(E18A-I4)") (class "Default")
      (node (ref "E18") (pin "5") (pinfunction "I4_5") (pintype "input"))
      (node (ref "FIELDS") (pin "10") (pinfunction "10_10") (pintype "passive"))
    )
    (net (code "81") (name "Net-(E18A-I5)") (class "Default")
      (node (ref "E18") (pin "6") (pinfunction "I5_6") (pintype "input"))
      (node (ref "FIELDS") (pin "12") (pinfunction "12_12") (pintype "passive"))
    )
    (net (code "82") (name "Net-(E18A-I6)") (class "Default")
      (node (ref "E18") (pin "11") (pinfunction "I6_11") (pintype "input"))
      (node (ref "FIELDS") (pin "16") (pinfunction "16_16") (pintype "passive"))
    )
    (net (code "83") (name "Net-(E18A-I7)") (class "Default")
      (node (ref "E18") (pin "12") (pinfunction "I7_12") (pintype "input"))
      (node (ref "FIELDS") (pin "14") (pinfunction "14_14") (pintype "passive"))
    )
    (net (code "84") (name "Net-(E19A-Y0)") (class "Default")
      (node (ref "E19") (pin "15") (pinfunction "Y0_15") (pintype "output"))
      (node (ref "FIELDS") (pin "1") (pinfunction "1_1") (pintype "passive"))
    )
    (net (code "85") (name "Net-(E19A-Y1)") (class "Default")
      (node (ref "E19") (pin "14") (pinfunction "Y1_14") (pintype "output"))
      (node (ref "FIELDS") (pin "3") (pinfunction "3_3") (pintype "passive"))
    )
    (net (code "86") (name "Net-(E19A-Y2)") (class "Default")
      (node (ref "E19") (pin "13") (pinfunction "Y2_13") (pintype "output"))
      (node (ref "FIELDS") (pin "5") (pinfunction "5_5") (pintype "passive"))
    )
    (net (code "87") (name "Net-(E19A-Y3)") (class "Default")
      (node (ref "E19") (pin "12") (pinfunction "Y3_12") (pintype "output"))
      (node (ref "FIELDS") (pin "7") (pinfunction "7_7") (pintype "passive"))
    )
    (net (code "88") (name "Net-(E19A-Y4)") (class "Default")
      (node (ref "E19") (pin "11") (pinfunction "Y4_11") (pintype "output"))
      (node (ref "FIELDS") (pin "9") (pinfunction "9_9") (pintype "passive"))
    )
    (net (code "89") (name "Net-(E19A-Y5)") (class "Default")
      (node (ref "E19") (pin "10") (pinfunction "Y5_10") (pintype "output"))
      (node (ref "FIELDS") (pin "11") (pinfunction "11_11") (pintype "passive"))
    )
    (net (code "90") (name "Net-(E19A-Y6)") (class "Default")
      (node (ref "E19") (pin "9") (pinfunction "Y6_9") (pintype "output"))
      (node (ref "FIELDS") (pin "13") (pinfunction "13_13") (pintype "passive"))
    )
    (net (code "91") (name "Net-(E19A-Y7)") (class "Default")
      (node (ref "E19") (pin "7") (pinfunction "Y7_7") (pintype "output"))
      (node (ref "FIELDS") (pin "15") (pinfunction "15_15") (pintype "passive"))
    )
    (net (code "92") (name "OE(0)") (class "Default")
      (node (ref "E11") (pin "6") (pinfunction "~{Q}_6") (pintype "output"))
      (node (ref "E12") (pin "1") (pinfunction "G_1") (pintype "input"))
      (node (ref "E12") (pin "19") (pinfunction "G_19") (pintype "input"))
      (node (ref "E13") (pin "1") (pinfunction "G_1") (pintype "input"))
      (node (ref "E13") (pin "19") (pinfunction "G_19") (pintype "input"))
      (node (ref "E16") (pin "22") (pinfunction "~{OE}_22") (pintype "input"))
      (node (ref "E16A") (pin "22") (pinfunction "~{OE}_22") (pintype "input"))
      (node (ref "E17") (pin "22") (pinfunction "~{OE}_22") (pintype "input"))
      (node (ref "E17A") (pin "22") (pinfunction "~{OE}_22") (pintype "input"))
      (node (ref "SV2") (pin "22") (pinfunction "22_22") (pintype "passive"))
      (node (ref "SV4") (pin "22") (pinfunction "22_22") (pintype "passive"))
      (node (ref "SV5") (pin "22") (pinfunction "22_22") (pintype "passive"))
    )
    (net (code "93") (name "PARITY") (class "Default")
      (node (ref "E13") (pin "11") (pinfunction "A1_11") (pintype "input"))
      (node (ref "E13") (pin "13") (pinfunction "A2_13") (pintype "input"))
      (node (ref "E13") (pin "15") (pinfunction "A3_15") (pintype "input"))
      (node (ref "E13") (pin "17") (pinfunction "A4_17") (pintype "input"))
      (node (ref "E15") (pin "9") (pinfunction "Y1_9") (pintype "tri_state"))
      (node (ref "E16") (pin "16") (pinfunction "I/O4_16") (pintype "bidirectional"))
      (node (ref "E16A") (pin "16") (pinfunction "I/O4_16") (pintype "bidirectional"))
      (node (ref "SV2") (pin "3") (pinfunction "3_3") (pintype "passive"))
      (node (ref "SV3") (pin "3") (pinfunction "3_3") (pintype "passive"))
      (node (ref "SV4") (pin "3") (pinfunction "3_3") (pintype "passive"))
    )
    (net (code "94") (name "PWR_OK(0)") (class "Default")
      (node (ref "E5") (pin "13") (pinfunction "O_13") (pintype "open_collector"))
      (node (ref "R5") (pin "1") (pinfunction "1_1") (pintype "passive"))
      (node (ref "RESET") (pin "1") (pinfunction "1_1") (pintype "passive"))
    )
    (net (code "95") (name "RESET") (class "Default")
      (node (ref "E1") (pin "8") (pinfunction "O_8") (pintype "output"))
      (node (ref "E10") (pin "11") (pinfunction "CLK_11") (pintype "input"))
      (node (ref "E10") (pin "3") (pinfunction "CLK_3") (pintype "input"))
      (node (ref "E11") (pin "3") (pinfunction "CLK_3") (pintype "input"))
      (node (ref "E9") (pin "3") (pinfunction "CLK_3") (pintype "input"))
    )
    (net (code "96") (name "STROBE(0)") (class "Default")
      (node (ref "E5") (pin "4") (pinfunction "O_4") (pintype "open_collector"))
      (node (ref "H05") (pin "P2") (pinfunction "1_P2") (pintype "bidirectional"))
    )
    (net (code "97") (name "STROBE(1)") (class "Default")
      (node (ref "E10") (pin "5") (pinfunction "Q_5") (pintype "output"))
      (node (ref "E5") (pin "5") (pinfunction "I0_5") (pintype "input"))
      (node (ref "E5") (pin "6") (pinfunction "I1_6") (pintype "input"))
    )
    (net (code "98") (name "TP150") (class "Default")
      (node (ref "E10") (pin "10") (pinfunction "PRE_10") (pintype "input"))
      (node (ref "E8") (pin "6") (pinfunction "TAP3_6") (pintype "output"))
    )
    (net (code "99") (name "TP250") (class "Default")
      (node (ref "E7") (pin "1") (pinfunction "IN_1") (pintype "input"))
      (node (ref "E8") (pin "5") (pinfunction "TAP5_5") (pintype "output"))
    )
    (net (code "100") (name "TP300") (class "Default")
      (node (ref "E10") (pin "13") (pinfunction "CLR_13") (pintype "input"))
      (node (ref "E7") (pin "7") (pinfunction "TAP1_7") (pintype "output"))
    )
    (net (code "101") (name "TP500") (class "Default")
      (node (ref "E11") (pin "13") (pinfunction "CLR_13") (pintype "input"))
      (node (ref "E6") (pin "1") (pinfunction "IN_1") (pintype "input"))
      (node (ref "E7") (pin "5") (pinfunction "TAP5_5") (pintype "output"))
      (node (ref "E9") (pin "4") (pinfunction "PRE_4") (pintype "input"))
    )
    (net (code "102") (name "TP550") (class "Default")
      (node (ref "E6") (pin "7") (pinfunction "TAP1_7") (pintype "output"))
      (node (ref "E9") (pin "1") (pinfunction "CLR_1") (pintype "input"))
    )
    (net (code "103") (name "VCC") (class "Default")
      (node (ref "C10") (pin "1") (pinfunction "1_1") (pintype "passive"))
      (node (ref "C11") (pin "1") (pinfunction "1_1") (pintype "passive"))
      (node (ref "C12") (pin "1") (pinfunction "1_1") (pintype "passive"))
      (node (ref "C13") (pin "1") (pinfunction "1_1") (pintype "passive"))
      (node (ref "C14") (pin "1") (pinfunction "1_1") (pintype "passive"))
      (node (ref "C15") (pin "1") (pinfunction "1_1") (pintype "passive"))
      (node (ref "C16") (pin "1") (pinfunction "1_1") (pintype "passive"))
      (node (ref "C2") (pin "1") (pinfunction "1_1") (pintype "passive"))
      (node (ref "C3") (pin "1") (pinfunction "1_1") (pintype "passive"))
      (node (ref "C4") (pin "1") (pinfunction "1_1") (pintype "passive"))
      (node (ref "C5") (pin "1") (pinfunction "1_1") (pintype "passive"))
      (node (ref "C6") (pin "1") (pinfunction "1_1") (pintype "passive"))
      (node (ref "C7") (pin "1") (pinfunction "1_1") (pintype "passive"))
      (node (ref "C8") (pin "1") (pinfunction "1_1") (pintype "passive"))
      (node (ref "C9") (pin "1") (pinfunction "1_1") (pintype "passive"))
      (node (ref "D1") (pin "C") (pinfunction "C_C") (pintype "passive"))
      (node (ref "E11") (pin "10") (pinfunction "PRE_10") (pintype "input"))
      (node (ref "E16") (pin "28") (pinfunction "VCC_28") (pintype "power_in"))
      (node (ref "E16A") (pin "28") (pinfunction "VCC_28") (pintype "power_in"))
      (node (ref "E17") (pin "28") (pinfunction "VCC_28") (pintype "power_in"))
      (node (ref "E17A") (pin "28") (pinfunction "VCC_28") (pintype "power_in"))
      (node (ref "E19") (pin "6") (pinfunction "G1_6") (pintype "input"))
      (node (ref "E5") (pin "8") (pinfunction "I0_8") (pintype "input"))
      (node (ref "E5") (pin "9") (pinfunction "I1_9") (pintype "input"))
      (node (ref "E9") (pin "10") (pinfunction "PRE_10") (pintype "input"))
      (node (ref "E9") (pin "11") (pinfunction "CLK_11") (pintype "input"))
      (node (ref "E9") (pin "12") (pinfunction "D_12") (pintype "input"))
      (node (ref "E9") (pin "13") (pinfunction "CLR_13") (pintype "input"))
      (node (ref "R3") (pin "2") (pinfunction "2_2") (pintype "passive"))
      (node (ref "R5") (pin "2") (pinfunction "2_2") (pintype "passive"))
      (node (ref "SV1") (pin "49") (pinfunction "49_49") (pintype "passive"))
      (node (ref "SV1") (pin "50") (pinfunction "50_50") (pintype "passive"))
      (node (ref "SV2") (pin "49") (pinfunction "49_49") (pintype "passive"))
      (node (ref "SV2") (pin "50") (pinfunction "50_50") (pintype "passive"))
      (node (ref "SV3") (pin "49") (pinfunction "49_49") (pintype "passive"))
      (node (ref "SV3") (pin "50") (pinfunction "50_50") (pintype "passive"))
      (node (ref "SV4") (pin "49") (pinfunction "49_49") (pintype "passive"))
      (node (ref "SV4") (pin "50") (pinfunction "50_50") (pintype "passive"))
      (node (ref "SV5") (pin "49") (pinfunction "49_49") (pintype "passive"))
      (node (ref "SV5") (pin "50") (pinfunction "50_50") (pintype "passive"))
      (node (ref "X1") (pin "1") (pinfunction "KL_1") (pintype "passive"))
    )
    (net (code "104") (name "WE(0)") (class "Default")
      (node (ref "E10") (pin "8") (pinfunction "~{Q}_8") (pintype "output"))
      (node (ref "E14") (pin "1") (pinfunction "G_1") (pintype "input"))
      (node (ref "E14") (pin "19") (pinfunction "G_19") (pintype "input"))
      (node (ref "E15") (pin "1") (pinfunction "G_1") (pintype "input"))
      (node (ref "E15") (pin "19") (pinfunction "G_19") (pintype "input"))
      (node (ref "E16") (pin "27") (pinfunction "~{WE}_27") (pintype "input"))
      (node (ref "E16A") (pin "27") (pinfunction "~{WE}_27") (pintype "input"))
      (node (ref "E17") (pin "27") (pinfunction "~{WE}_27") (pintype "input"))
      (node (ref "E17A") (pin "27") (pinfunction "~{WE}_27") (pintype "input"))
      (node (ref "SV2") (pin "32") (pinfunction "32_32") (pintype "passive"))
      (node (ref "SV3") (pin "32") (pinfunction "32_32") (pintype "passive"))
      (node (ref "SV5") (pin "32") (pinfunction "32_32") (pintype "passive"))
    )
    (net (code "105") (name "unconnected-(E2A-TAP1-Pad7)") (class "Default")
      (node (ref "E2") (pin "7") (pinfunction "TAP1_7") (pintype "output"))
    )
    (net (code "106") (name "unconnected-(E2A-TAP2-Pad2)") (class "Default")
      (node (ref "E2") (pin "2") (pinfunction "TAP2_2") (pintype "output"))
    )
    (net (code "107") (name "unconnected-(E2A-TAP4-Pad3)") (class "Default")
      (node (ref "E2") (pin "3") (pinfunction "TAP4_3") (pintype "output"))
    )
    (net (code "108") (name "unconnected-(E2A-TAP5-Pad5)") (class "Default")
      (node (ref "E2") (pin "5") (pinfunction "TAP5_5") (pintype "output"))
    )
    (net (code "109") (name "unconnected-(E3A-TAP1-Pad7)") (class "Default")
      (node (ref "E3") (pin "7") (pinfunction "TAP1_7") (pintype "output"))
    )
    (net (code "110") (name "unconnected-(E3A-TAP4-Pad3)") (class "Default")
      (node (ref "E3") (pin "3") (pinfunction "TAP4_3") (pintype "output"))
    )
    (net (code "111") (name "unconnected-(E4A-TAP1-Pad7)") (class "Default")
      (node (ref "E4") (pin "7") (pinfunction "TAP1_7") (pintype "output"))
    )
    (net (code "112") (name "unconnected-(E4A-TAP4-Pad3)") (class "Default")
      (node (ref "E4") (pin "3") (pinfunction "TAP4_3") (pintype "output"))
    )
    (net (code "113") (name "unconnected-(E5C-O-Pad10)") (class "Default")
      (node (ref "E5") (pin "10") (pinfunction "O_10") (pintype "open_collector"))
    )
    (net (code "114") (name "unconnected-(E6A-TAP2-Pad2)") (class "Default")
      (node (ref "E6") (pin "2") (pinfunction "TAP2_2") (pintype "output"))
    )
    (net (code "115") (name "unconnected-(E6A-TAP3-Pad6)") (class "Default")
      (node (ref "E6") (pin "6") (pinfunction "TAP3_6") (pintype "output"))
    )
    (net (code "116") (name "unconnected-(E6A-TAP4-Pad3)") (class "Default")
      (node (ref "E6") (pin "3") (pinfunction "TAP4_3") (pintype "output"))
    )
    (net (code "117") (name "unconnected-(E6A-TAP5-Pad5)") (class "Default")
      (node (ref "E6") (pin "5") (pinfunction "TAP5_5") (pintype "output"))
    )
    (net (code "118") (name "unconnected-(E7A-TAP2-Pad2)") (class "Default")
      (node (ref "E7") (pin "2") (pinfunction "TAP2_2") (pintype "output"))
    )
    (net (code "119") (name "unconnected-(E7A-TAP3-Pad6)") (class "Default")
      (node (ref "E7") (pin "6") (pinfunction "TAP3_6") (pintype "output"))
    )
    (net (code "120") (name "unconnected-(E7A-TAP4-Pad3)") (class "Default")
      (node (ref "E7") (pin "3") (pinfunction "TAP4_3") (pintype "output"))
    )
    (net (code "121") (name "unconnected-(E8A-TAP1-Pad7)") (class "Default")
      (node (ref "E8") (pin "7") (pinfunction "TAP1_7") (pintype "output"))
    )
    (net (code "122") (name "unconnected-(E8A-TAP2-Pad2)") (class "Default")
      (node (ref "E8") (pin "2") (pinfunction "TAP2_2") (pintype "output"))
    )
    (net (code "123") (name "unconnected-(E8A-TAP4-Pad3)") (class "Default")
      (node (ref "E8") (pin "3") (pinfunction "TAP4_3") (pintype "output"))
    )
    (net (code "124") (name "unconnected-(E9A-~{Q}-Pad6)") (class "Default")
      (node (ref "E9") (pin "6") (pinfunction "~{Q}_6") (pintype "output"))
    )
    (net (code "125") (name "unconnected-(E9B-Q-Pad9)") (class "Default")
      (node (ref "E9") (pin "9") (pinfunction "Q_9") (pintype "output"))
    )
    (net (code "126") (name "unconnected-(E9B-~{Q}-Pad8)") (class "Default")
      (node (ref "E9") (pin "8") (pinfunction "~{Q}_8") (pintype "output"))
    )
    (net (code "127") (name "unconnected-(E10A-~{Q}-Pad6)") (class "Default")
      (node (ref "E10") (pin "6") (pinfunction "~{Q}_6") (pintype "output"))
    )
    (net (code "128") (name "unconnected-(E10B-Q-Pad9)") (class "Default")
      (node (ref "E10") (pin "9") (pinfunction "Q_9") (pintype "output"))
    )
    (net (code "129") (name "unconnected-(E11A-Q-Pad5)") (class "Default")
      (node (ref "E11") (pin "5") (pinfunction "Q_5") (pintype "output"))
    )
    (net (code "130") (name "unconnected-(E11B-Q-Pad9)") (class "Default")
      (node (ref "E11") (pin "9") (pinfunction "Q_9") (pintype "output"))
    )
    (net (code "131") (name "unconnected-(E13B-Y2-Pad7)") (class "Default")
      (node (ref "E13") (pin "7") (pinfunction "Y2_7") (pintype "tri_state"))
    )
    (net (code "132") (name "unconnected-(E13B-Y3-Pad5)") (class "Default")
      (node (ref "E13") (pin "5") (pinfunction "Y3_5") (pintype "tri_state"))
    )
    (net (code "133") (name "unconnected-(E13B-Y4-Pad3)") (class "Default")
      (node (ref "E13") (pin "3") (pinfunction "Y4_3") (pintype "tri_state"))
    )
    (net (code "134") (name "unconnected-(E15B-Y2-Pad7)") (class "Default")
      (node (ref "E15") (pin "7") (pinfunction "Y2_7") (pintype "tri_state"))
    )
    (net (code "135") (name "unconnected-(E15B-Y3-Pad5)") (class "Default")
      (node (ref "E15") (pin "5") (pinfunction "Y3_5") (pintype "tri_state"))
    )
    (net (code "136") (name "unconnected-(E15B-Y4-Pad3)") (class "Default")
      (node (ref "E15") (pin "3") (pinfunction "Y4_3") (pintype "tri_state"))
    )
    (net (code "137") (name "unconnected-(SV1-Pad3)") (class "Default")
      (node (ref "SV1") (pin "3") (pinfunction "3_3") (pintype "passive"))
    )
    (net (code "138") (name "unconnected-(SV1-Pad4)") (class "Default")
      (node (ref "SV1") (pin "4") (pinfunction "4_4") (pintype "passive"))
    )
    (net (code "139") (name "unconnected-(SV1-Pad5)") (class "Default")
      (node (ref "SV1") (pin "5") (pinfunction "5_5") (pintype "passive"))
    )
    (net (code "140") (name "unconnected-(SV1-Pad6)") (class "Default")
      (node (ref "SV1") (pin "6") (pinfunction "6_6") (pintype "passive"))
    )
    (net (code "141") (name "unconnected-(SV1-Pad7)") (class "Default")
      (node (ref "SV1") (pin "7") (pinfunction "7_7") (pintype "passive"))
    )
    (net (code "142") (name "unconnected-(SV1-Pad8)") (class "Default")
      (node (ref "SV1") (pin "8") (pinfunction "8_8") (pintype "passive"))
    )
    (net (code "143") (name "unconnected-(SV1-Pad9)") (class "Default")
      (node (ref "SV1") (pin "9") (pinfunction "9_9") (pintype "passive"))
    )
    (net (code "144") (name "unconnected-(SV1-Pad10)") (class "Default")
      (node (ref "SV1") (pin "10") (pinfunction "10_10") (pintype "passive"))
    )
    (net (code "145") (name "unconnected-(SV1-Pad11)") (class "Default")
      (node (ref "SV1") (pin "11") (pinfunction "11_11") (pintype "passive"))
    )
    (net (code "146") (name "unconnected-(SV1-Pad12)") (class "Default")
      (node (ref "SV1") (pin "12") (pinfunction "12_12") (pintype "passive"))
    )
    (net (code "147") (name "unconnected-(SV1-Pad13)") (class "Default")
      (node (ref "SV1") (pin "13") (pinfunction "13_13") (pintype "passive"))
    )
    (net (code "148") (name "unconnected-(SV1-Pad14)") (class "Default")
      (node (ref "SV1") (pin "14") (pinfunction "14_14") (pintype "passive"))
    )
    (net (code "149") (name "unconnected-(SV1-Pad15)") (class "Default")
      (node (ref "SV1") (pin "15") (pinfunction "15_15") (pintype "passive"))
    )
    (net (code "150") (name "unconnected-(SV1-Pad16)") (class "Default")
      (node (ref "SV1") (pin "16") (pinfunction "16_16") (pintype "passive"))
    )
    (net (code "151") (name "unconnected-(SV1-Pad17)") (class "Default")
      (node (ref "SV1") (pin "17") (pinfunction "17_17") (pintype "passive"))
    )
    (net (code "152") (name "unconnected-(SV1-Pad18)") (class "Default")
      (node (ref "SV1") (pin "18") (pinfunction "18_18") (pintype "passive"))
    )
    (net (code "153") (name "unconnected-(SV1-Pad19)") (class "Default")
      (node (ref "SV1") (pin "19") (pinfunction "19_19") (pintype "passive"))
    )
    (net (code "154") (name "unconnected-(SV1-Pad21)") (class "Default")
      (node (ref "SV1") (pin "21") (pinfunction "21_21") (pintype "passive"))
    )
    (net (code "155") (name "unconnected-(SV1-Pad22)") (class "Default")
      (node (ref "SV1") (pin "22") (pinfunction "22_22") (pintype "passive"))
    )
    (net (code "156") (name "unconnected-(SV1-Pad23)") (class "Default")
      (node (ref "SV1") (pin "23") (pinfunction "23_23") (pintype "passive"))
    )
    (net (code "157") (name "unconnected-(SV1-Pad25)") (class "Default")
      (node (ref "SV1") (pin "25") (pinfunction "25_25") (pintype "passive"))
    )
    (net (code "158") (name "unconnected-(SV1-Pad32)") (class "Default")
      (node (ref "SV1") (pin "32") (pinfunction "32_32") (pintype "passive"))
    )
    (net (code "159") (name "unconnected-(SV1-Pad35)") (class "Default")
      (node (ref "SV1") (pin "35") (pinfunction "35_35") (pintype "passive"))
    )
    (net (code "160") (name "unconnected-(SV1-Pad36)") (class "Default")
      (node (ref "SV1") (pin "36") (pinfunction "36_36") (pintype "passive"))
    )
    (net (code "161") (name "unconnected-(SV1-Pad37)") (class "Default")
      (node (ref "SV1") (pin "37") (pinfunction "37_37") (pintype "passive"))
    )
    (net (code "162") (name "unconnected-(SV1-Pad38)") (class "Default")
      (node (ref "SV1") (pin "38") (pinfunction "38_38") (pintype "passive"))
    )
    (net (code "163") (name "unconnected-(SV1-Pad39)") (class "Default")
      (node (ref "SV1") (pin "39") (pinfunction "39_39") (pintype "passive"))
    )
    (net (code "164") (name "unconnected-(SV1-Pad40)") (class "Default")
      (node (ref "SV1") (pin "40") (pinfunction "40_40") (pintype "passive"))
    )
    (net (code "165") (name "unconnected-(SV1-Pad41)") (class "Default")
      (node (ref "SV1") (pin "41") (pinfunction "41_41") (pintype "passive"))
    )
    (net (code "166") (name "unconnected-(SV1-Pad42)") (class "Default")
      (node (ref "SV1") (pin "42") (pinfunction "42_42") (pintype "passive"))
    )
    (net (code "167") (name "unconnected-(SV1-Pad45)") (class "Default")
      (node (ref "SV1") (pin "45") (pinfunction "45_45") (pintype "passive"))
    )
    (net (code "168") (name "unconnected-(SV1-Pad47)") (class "Default")
      (node (ref "SV1") (pin "47") (pinfunction "47_47") (pintype "passive"))
    )
    (net (code "169") (name "unconnected-(SV1-Pad48)") (class "Default")
      (node (ref "SV1") (pin "48") (pinfunction "48_48") (pintype "passive"))
    )
    (net (code "170") (name "unconnected-(SV2-Pad34)") (class "Default")
      (node (ref "SV2") (pin "34") (pinfunction "34_34") (pintype "passive"))
    )
    (net (code "171") (name "unconnected-(SV2-Pad37)") (class "Default")
      (node (ref "SV2") (pin "37") (pinfunction "37_37") (pintype "passive"))
    )
    (net (code "172") (name "unconnected-(SV2-Pad39)") (class "Default")
      (node (ref "SV2") (pin "39") (pinfunction "39_39") (pintype "passive"))
    )
    (net (code "173") (name "unconnected-(SV2-Pad40)") (class "Default")
      (node (ref "SV2") (pin "40") (pinfunction "40_40") (pintype "passive"))
    )
    (net (code "174") (name "unconnected-(SV2-Pad41)") (class "Default")
      (node (ref "SV2") (pin "41") (pinfunction "41_41") (pintype "passive"))
    )
    (net (code "175") (name "unconnected-(SV2-Pad42)") (class "Default")
      (node (ref "SV2") (pin "42") (pinfunction "42_42") (pintype "passive"))
    )
    (net (code "176") (name "unconnected-(SV2-Pad43)") (class "Default")
      (node (ref "SV2") (pin "43") (pinfunction "43_43") (pintype "passive"))
    )
    (net (code "177") (name "unconnected-(SV2-Pad44)") (class "Default")
      (node (ref "SV2") (pin "44") (pinfunction "44_44") (pintype "passive"))
    )
    (net (code "178") (name "unconnected-(SV2-Pad45)") (class "Default")
      (node (ref "SV2") (pin "45") (pinfunction "45_45") (pintype "passive"))
    )
    (net (code "179") (name "unconnected-(SV2-Pad46)") (class "Default")
      (node (ref "SV2") (pin "46") (pinfunction "46_46") (pintype "passive"))
    )
    (net (code "180") (name "unconnected-(SV2-Pad47)") (class "Default")
      (node (ref "SV2") (pin "47") (pinfunction "47_47") (pintype "passive"))
    )
    (net (code "181") (name "unconnected-(SV2-Pad48)") (class "Default")
      (node (ref "SV2") (pin "48") (pinfunction "48_48") (pintype "passive"))
    )
    (net (code "182") (name "unconnected-(SV3-Pad15)") (class "Default")
      (node (ref "SV3") (pin "15") (pinfunction "15_15") (pintype "passive"))
    )
    (net (code "183") (name "unconnected-(SV3-Pad17)") (class "Default")
      (node (ref "SV3") (pin "17") (pinfunction "17_17") (pintype "passive"))
    )
    (net (code "184") (name "unconnected-(SV3-Pad18)") (class "Default")
      (node (ref "SV3") (pin "18") (pinfunction "18_18") (pintype "passive"))
    )
    (net (code "185") (name "unconnected-(SV3-Pad19)") (class "Default")
      (node (ref "SV3") (pin "19") (pinfunction "19_19") (pintype "passive"))
    )
    (net (code "186") (name "unconnected-(SV3-Pad20)") (class "Default")
      (node (ref "SV3") (pin "20") (pinfunction "20_20") (pintype "passive"))
    )
    (net (code "187") (name "unconnected-(SV3-Pad21)") (class "Default")
      (node (ref "SV3") (pin "21") (pinfunction "21_21") (pintype "passive"))
    )
    (net (code "188") (name "unconnected-(SV3-Pad22)") (class "Default")
      (node (ref "SV3") (pin "22") (pinfunction "22_22") (pintype "passive"))
    )
    (net (code "189") (name "unconnected-(SV3-Pad23)") (class "Default")
      (node (ref "SV3") (pin "23") (pinfunction "23_23") (pintype "passive"))
    )
    (net (code "190") (name "unconnected-(SV3-Pad24)") (class "Default")
      (node (ref "SV3") (pin "24") (pinfunction "24_24") (pintype "passive"))
    )
    (net (code "191") (name "unconnected-(SV3-Pad25)") (class "Default")
      (node (ref "SV3") (pin "25") (pinfunction "25_25") (pintype "passive"))
    )
    (net (code "192") (name "unconnected-(SV3-Pad26)") (class "Default")
      (node (ref "SV3") (pin "26") (pinfunction "26_26") (pintype "passive"))
    )
    (net (code "193") (name "unconnected-(SV3-Pad27)") (class "Default")
      (node (ref "SV3") (pin "27") (pinfunction "27_27") (pintype "passive"))
    )
    (net (code "194") (name "unconnected-(SV3-Pad28)") (class "Default")
      (node (ref "SV3") (pin "28") (pinfunction "28_28") (pintype "passive"))
    )
    (net (code "195") (name "unconnected-(SV3-Pad29)") (class "Default")
      (node (ref "SV3") (pin "29") (pinfunction "29_29") (pintype "passive"))
    )
    (net (code "196") (name "unconnected-(SV3-Pad34)") (class "Default")
      (node (ref "SV3") (pin "34") (pinfunction "34_34") (pintype "passive"))
    )
    (net (code "197") (name "unconnected-(SV3-Pad37)") (class "Default")
      (node (ref "SV3") (pin "37") (pinfunction "37_37") (pintype "passive"))
    )
    (net (code "198") (name "unconnected-(SV3-Pad39)") (class "Default")
      (node (ref "SV3") (pin "39") (pinfunction "39_39") (pintype "passive"))
    )
    (net (code "199") (name "unconnected-(SV3-Pad40)") (class "Default")
      (node (ref "SV3") (pin "40") (pinfunction "40_40") (pintype "passive"))
    )
    (net (code "200") (name "unconnected-(SV3-Pad41)") (class "Default")
      (node (ref "SV3") (pin "41") (pinfunction "41_41") (pintype "passive"))
    )
    (net (code "201") (name "unconnected-(SV3-Pad45)") (class "Default")
      (node (ref "SV3") (pin "45") (pinfunction "45_45") (pintype "passive"))
    )
    (net (code "202") (name "unconnected-(SV3-Pad47)") (class "Default")
      (node (ref "SV3") (pin "47") (pinfunction "47_47") (pintype "passive"))
    )
    (net (code "203") (name "unconnected-(SV3-Pad48)") (class "Default")
      (node (ref "SV3") (pin "48") (pinfunction "48_48") (pintype "passive"))
    )
    (net (code "204") (name "unconnected-(SV4-Pad15)") (class "Default")
      (node (ref "SV4") (pin "15") (pinfunction "15_15") (pintype "passive"))
    )
    (net (code "205") (name "unconnected-(SV4-Pad17)") (class "Default")
      (node (ref "SV4") (pin "17") (pinfunction "17_17") (pintype "passive"))
    )
    (net (code "206") (name "unconnected-(SV4-Pad18)") (class "Default")
      (node (ref "SV4") (pin "18") (pinfunction "18_18") (pintype "passive"))
    )
    (net (code "207") (name "unconnected-(SV4-Pad19)") (class "Default")
      (node (ref "SV4") (pin "19") (pinfunction "19_19") (pintype "passive"))
    )
    (net (code "208") (name "unconnected-(SV4-Pad20)") (class "Default")
      (node (ref "SV4") (pin "20") (pinfunction "20_20") (pintype "passive"))
    )
    (net (code "209") (name "unconnected-(SV4-Pad21)") (class "Default")
      (node (ref "SV4") (pin "21") (pinfunction "21_21") (pintype "passive"))
    )
    (net (code "210") (name "unconnected-(SV4-Pad23)") (class "Default")
      (node (ref "SV4") (pin "23") (pinfunction "23_23") (pintype "passive"))
    )
    (net (code "211") (name "unconnected-(SV4-Pad24)") (class "Default")
      (node (ref "SV4") (pin "24") (pinfunction "24_24") (pintype "passive"))
    )
    (net (code "212") (name "unconnected-(SV4-Pad25)") (class "Default")
      (node (ref "SV4") (pin "25") (pinfunction "25_25") (pintype "passive"))
    )
    (net (code "213") (name "unconnected-(SV4-Pad26)") (class "Default")
      (node (ref "SV4") (pin "26") (pinfunction "26_26") (pintype "passive"))
    )
    (net (code "214") (name "unconnected-(SV4-Pad27)") (class "Default")
      (node (ref "SV4") (pin "27") (pinfunction "27_27") (pintype "passive"))
    )
    (net (code "215") (name "unconnected-(SV4-Pad28)") (class "Default")
      (node (ref "SV4") (pin "28") (pinfunction "28_28") (pintype "passive"))
    )
    (net (code "216") (name "unconnected-(SV4-Pad29)") (class "Default")
      (node (ref "SV4") (pin "29") (pinfunction "29_29") (pintype "passive"))
    )
    (net (code "217") (name "unconnected-(SV4-Pad30)") (class "Default")
      (node (ref "SV4") (pin "30") (pinfunction "30_30") (pintype "passive"))
    )
    (net (code "218") (name "unconnected-(SV4-Pad31)") (class "Default")
      (node (ref "SV4") (pin "31") (pinfunction "31_31") (pintype "passive"))
    )
    (net (code "219") (name "unconnected-(SV4-Pad32)") (class "Default")
      (node (ref "SV4") (pin "32") (pinfunction "32_32") (pintype "passive"))
    )
    (net (code "220") (name "unconnected-(SV4-Pad33)") (class "Default")
      (node (ref "SV4") (pin "33") (pinfunction "33_33") (pintype "passive"))
    )
    (net (code "221") (name "unconnected-(SV4-Pad34)") (class "Default")
      (node (ref "SV4") (pin "34") (pinfunction "34_34") (pintype "passive"))
    )
    (net (code "222") (name "unconnected-(SV4-Pad35)") (class "Default")
      (node (ref "SV4") (pin "35") (pinfunction "35_35") (pintype "passive"))
    )
    (net (code "223") (name "unconnected-(SV4-Pad36)") (class "Default")
      (node (ref "SV4") (pin "36") (pinfunction "36_36") (pintype "passive"))
    )
    (net (code "224") (name "unconnected-(SV4-Pad38)") (class "Default")
      (node (ref "SV4") (pin "38") (pinfunction "38_38") (pintype "passive"))
    )
    (net (code "225") (name "unconnected-(SV4-Pad42)") (class "Default")
      (node (ref "SV4") (pin "42") (pinfunction "42_42") (pintype "passive"))
    )
    (net (code "226") (name "unconnected-(SV4-Pad43)") (class "Default")
      (node (ref "SV4") (pin "43") (pinfunction "43_43") (pintype "passive"))
    )
    (net (code "227") (name "unconnected-(SV4-Pad44)") (class "Default")
      (node (ref "SV4") (pin "44") (pinfunction "44_44") (pintype "passive"))
    )
    (net (code "228") (name "unconnected-(SV4-Pad45)") (class "Default")
      (node (ref "SV4") (pin "45") (pinfunction "45_45") (pintype "passive"))
    )
    (net (code "229") (name "unconnected-(SV4-Pad46)") (class "Default")
      (node (ref "SV4") (pin "46") (pinfunction "46_46") (pintype "passive"))
    )
    (net (code "230") (name "unconnected-(SV4-Pad47)") (class "Default")
      (node (ref "SV4") (pin "47") (pinfunction "47_47") (pintype "passive"))
    )
    (net (code "231") (name "unconnected-(SV4-Pad48)") (class "Default")
      (node (ref "SV4") (pin "48") (pinfunction "48_48") (pintype "passive"))
    )
    (net (code "232") (name "unconnected-(SV5-Pad3)") (class "Default")
      (node (ref "SV5") (pin "3") (pinfunction "3_3") (pintype "passive"))
    )
    (net (code "233") (name "unconnected-(SV5-Pad4)") (class "Default")
      (node (ref "SV5") (pin "4") (pinfunction "4_4") (pintype "passive"))
    )
    (net (code "234") (name "unconnected-(SV5-Pad5)") (class "Default")
      (node (ref "SV5") (pin "5") (pinfunction "5_5") (pintype "passive"))
    )
    (net (code "235") (name "unconnected-(SV5-Pad6)") (class "Default")
      (node (ref "SV5") (pin "6") (pinfunction "6_6") (pintype "passive"))
    )
    (net (code "236") (name "unconnected-(SV5-Pad7)") (class "Default")
      (node (ref "SV5") (pin "7") (pinfunction "7_7") (pintype "passive"))
    )
    (net (code "237") (name "unconnected-(SV5-Pad8)") (class "Default")
      (node (ref "SV5") (pin "8") (pinfunction "8_8") (pintype "passive"))
    )
    (net (code "238") (name "unconnected-(SV5-Pad9)") (class "Default")
      (node (ref "SV5") (pin "9") (pinfunction "9_9") (pintype "passive"))
    )
    (net (code "239") (name "unconnected-(SV5-Pad10)") (class "Default")
      (node (ref "SV5") (pin "10") (pinfunction "10_10") (pintype "passive"))
    )
    (net (code "240") (name "unconnected-(SV5-Pad11)") (class "Default")
      (node (ref "SV5") (pin "11") (pinfunction "11_11") (pintype "passive"))
    )
    (net (code "241") (name "unconnected-(SV5-Pad12)") (class "Default")
      (node (ref "SV5") (pin "12") (pinfunction "12_12") (pintype "passive"))
    )
    (net (code "242") (name "unconnected-(SV5-Pad13)") (class "Default")
      (node (ref "SV5") (pin "13") (pinfunction "13_13") (pintype "passive"))
    )
    (net (code "243") (name "unconnected-(SV5-Pad14)") (class "Default")
      (node (ref "SV5") (pin "14") (pinfunction "14_14") (pintype "passive"))
    )
    (net (code "244") (name "unconnected-(SV5-Pad15)") (class "Default")
      (node (ref "SV5") (pin "15") (pinfunction "15_15") (pintype "passive"))
    )
    (net (code "245") (name "unconnected-(SV5-Pad16)") (class "Default")
      (node (ref "SV5") (pin "16") (pinfunction "16_16") (pintype "passive"))
    )
    (net (code "246") (name "unconnected-(SV5-Pad17)") (class "Default")
      (node (ref "SV5") (pin "17") (pinfunction "17_17") (pintype "passive"))
    )
    (net (code "247") (name "unconnected-(SV5-Pad19)") (class "Default")
      (node (ref "SV5") (pin "19") (pinfunction "19_19") (pintype "passive"))
    )
    (net (code "248") (name "unconnected-(SV5-Pad20)") (class "Default")
      (node (ref "SV5") (pin "20") (pinfunction "20_20") (pintype "passive"))
    )
    (net (code "249") (name "unconnected-(SV5-Pad21)") (class "Default")
      (node (ref "SV5") (pin "21") (pinfunction "21_21") (pintype "passive"))
    )
    (net (code "250") (name "unconnected-(SV5-Pad23)") (class "Default")
      (node (ref "SV5") (pin "23") (pinfunction "23_23") (pintype "passive"))
    )
    (net (code "251") (name "unconnected-(SV5-Pad24)") (class "Default")
      (node (ref "SV5") (pin "24") (pinfunction "24_24") (pintype "passive"))
    )
    (net (code "252") (name "unconnected-(SV5-Pad25)") (class "Default")
      (node (ref "SV5") (pin "25") (pinfunction "25_25") (pintype "passive"))
    )
    (net (code "253") (name "unconnected-(SV5-Pad26)") (class "Default")
      (node (ref "SV5") (pin "26") (pinfunction "26_26") (pintype "passive"))
    )
    (net (code "254") (name "unconnected-(SV5-Pad27)") (class "Default")
      (node (ref "SV5") (pin "27") (pinfunction "27_27") (pintype "passive"))
    )
    (net (code "255") (name "unconnected-(SV5-Pad28)") (class "Default")
      (node (ref "SV5") (pin "28") (pinfunction "28_28") (pintype "passive"))
    )
    (net (code "256") (name "unconnected-(SV5-Pad29)") (class "Default")
      (node (ref "SV5") (pin "29") (pinfunction "29_29") (pintype "passive"))
    )
    (net (code "257") (name "unconnected-(SV5-Pad30)") (class "Default")
      (node (ref "SV5") (pin "30") (pinfunction "30_30") (pintype "passive"))
    )
    (net (code "258") (name "unconnected-(SV5-Pad31)") (class "Default")
      (node (ref "SV5") (pin "31") (pinfunction "31_31") (pintype "passive"))
    )
    (net (code "259") (name "unconnected-(SV5-Pad33)") (class "Default")
      (node (ref "SV5") (pin "33") (pinfunction "33_33") (pintype "passive"))
    )
    (net (code "260") (name "unconnected-(SV5-Pad35)") (class "Default")
      (node (ref "SV5") (pin "35") (pinfunction "35_35") (pintype "passive"))
    )
    (net (code "261") (name "unconnected-(SV5-Pad36)") (class "Default")
      (node (ref "SV5") (pin "36") (pinfunction "36_36") (pintype "passive"))
    )
    (net (code "262") (name "unconnected-(SV5-Pad38)") (class "Default")
      (node (ref "SV5") (pin "38") (pinfunction "38_38") (pintype "passive"))
    )
    (net (code "263") (name "unconnected-(SV5-Pad43)") (class "Default")
      (node (ref "SV5") (pin "43") (pinfunction "43_43") (pintype "passive"))
    )
    (net (code "264") (name "unconnected-(SV5-Pad44)") (class "Default")
      (node (ref "SV5") (pin "44") (pinfunction "44_44") (pintype "passive"))
    )
    (net (code "265") (name "unconnected-(SV5-Pad45)") (class "Default")
      (node (ref "SV5") (pin "45") (pinfunction "45_45") (pintype "passive"))
    )
    (net (code "266") (name "unconnected-(SV5-Pad46)") (class "Default")
      (node (ref "SV5") (pin "46") (pinfunction "46_46") (pintype "passive"))
    )
    (net (code "267") (name "unconnected-(SV5-Pad47)") (class "Default")
      (node (ref "SV5") (pin "47") (pinfunction "47_47") (pintype "passive"))
    )
    (net (code "268") (name "unconnected-(SV5-Pad48)") (class "Default")
      (node (ref "SV5") (pin "48") (pinfunction "48_48") (pintype "passive"))
    )
  )
)
